# Led_Beleuchtung.net
KiCad netlist of a schematic drawn in EAGLE
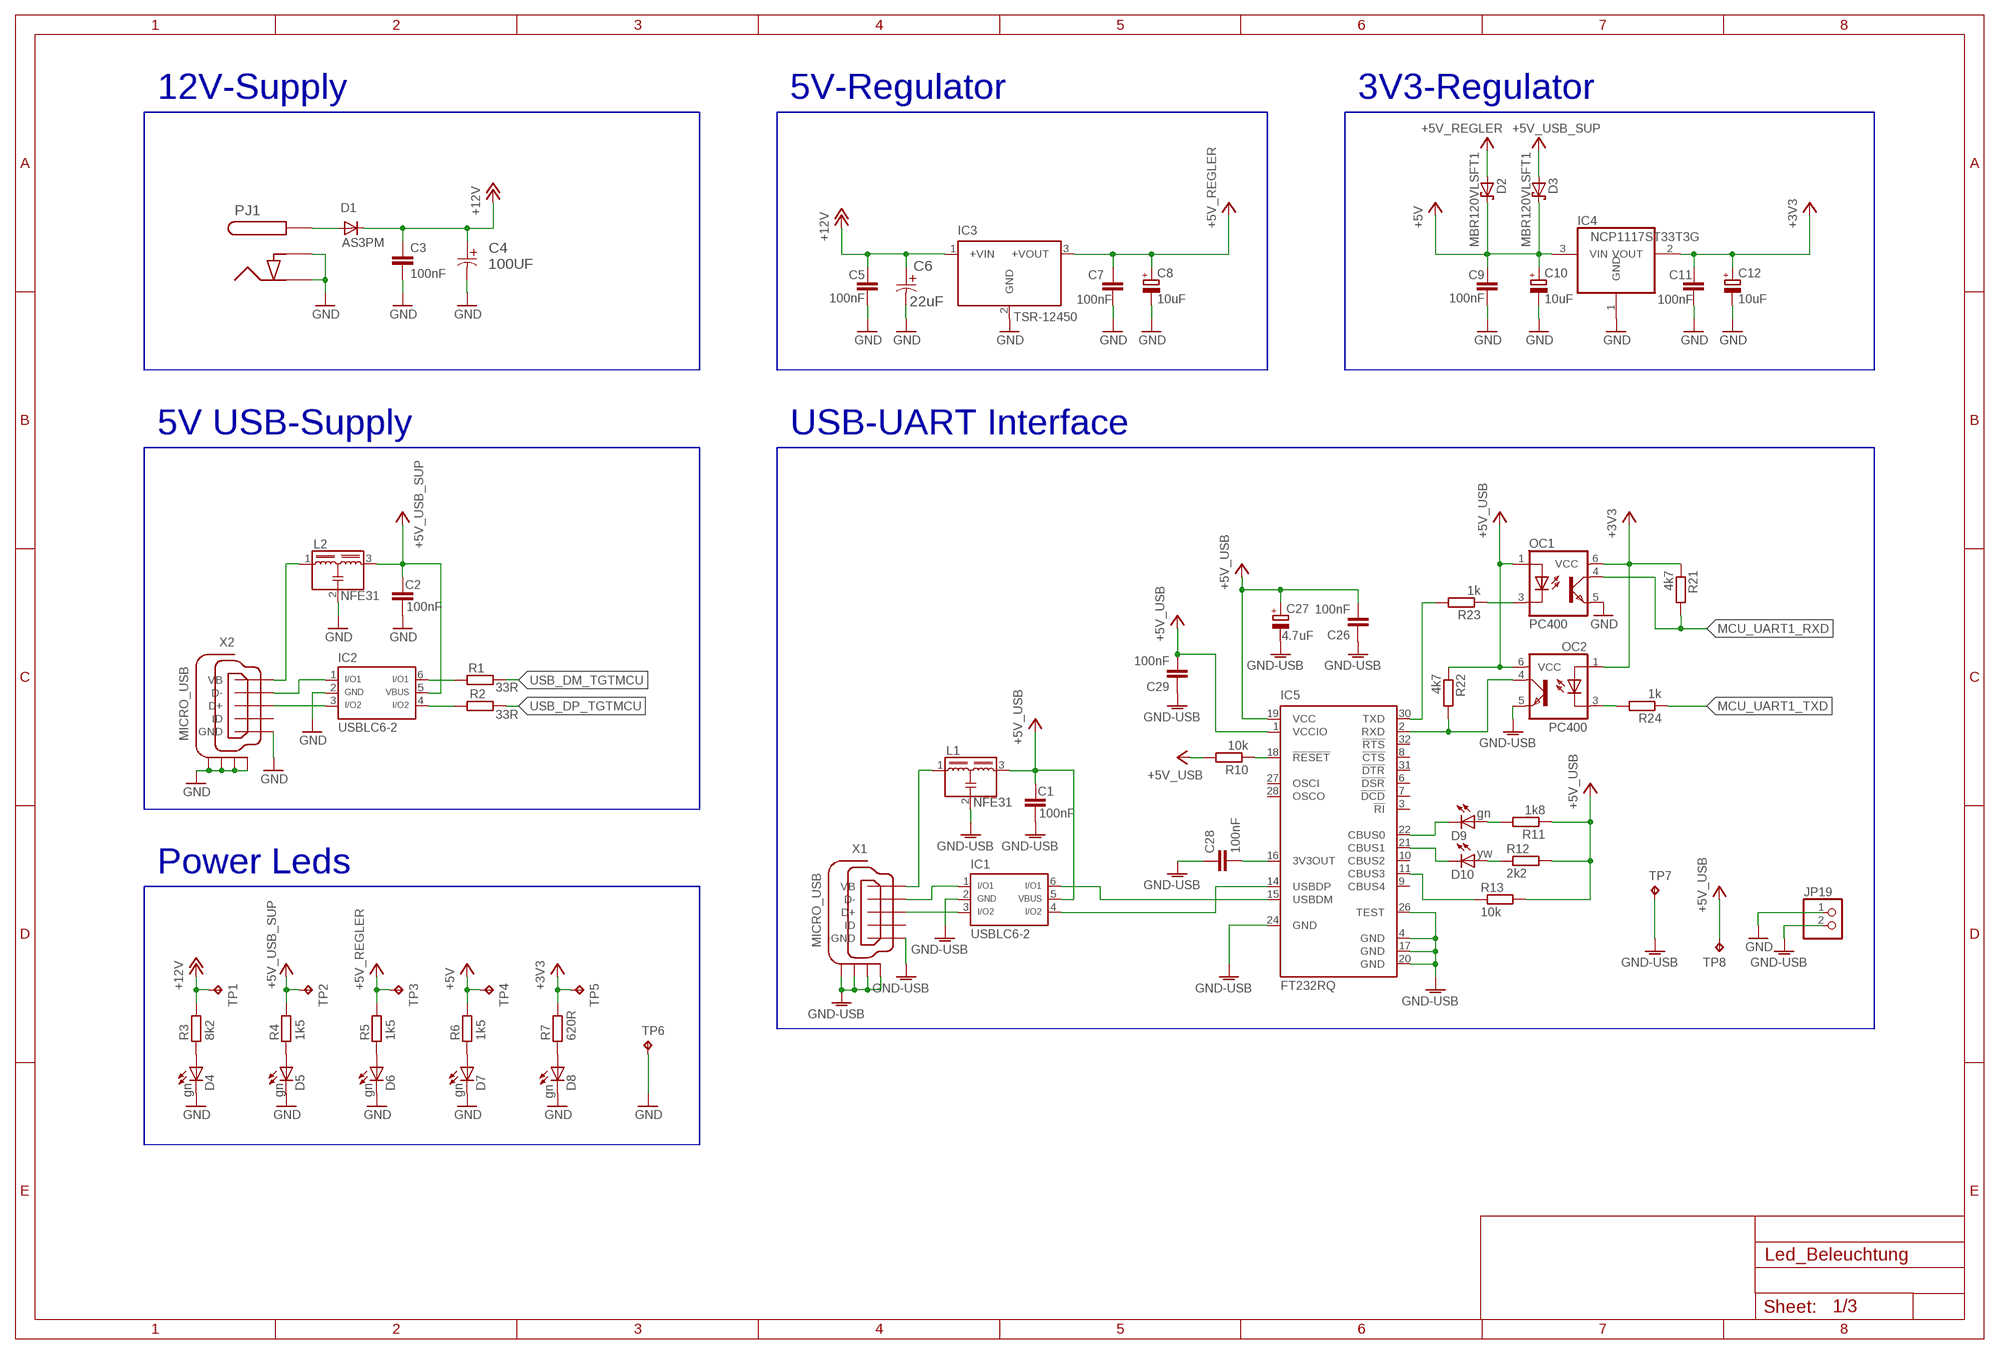
[diagram p0: schematic, sheet 1]
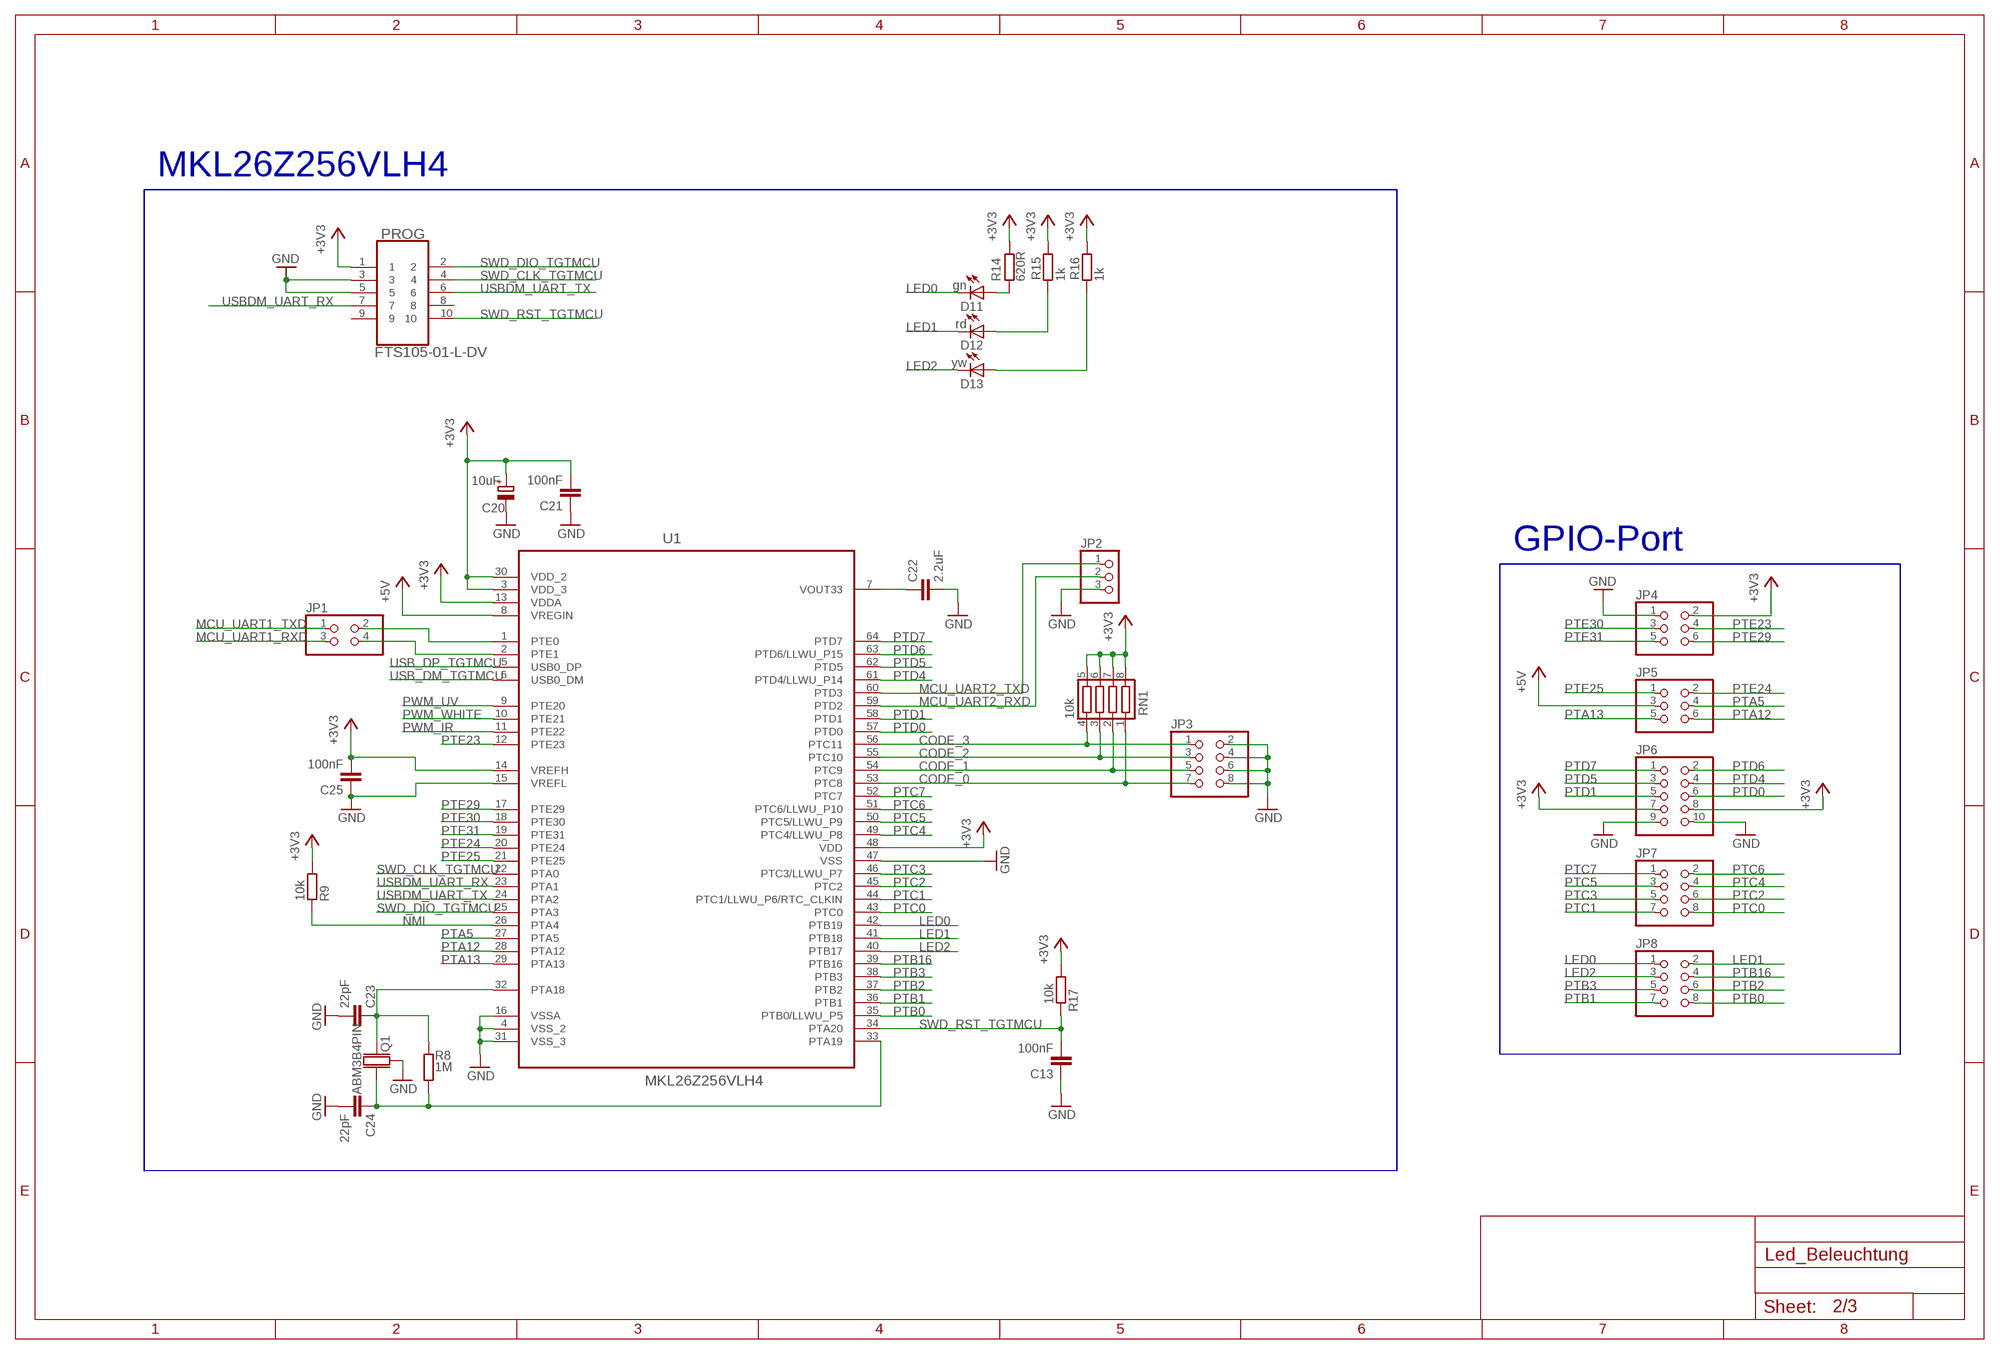
[diagram p1: schematic, sheet 2]
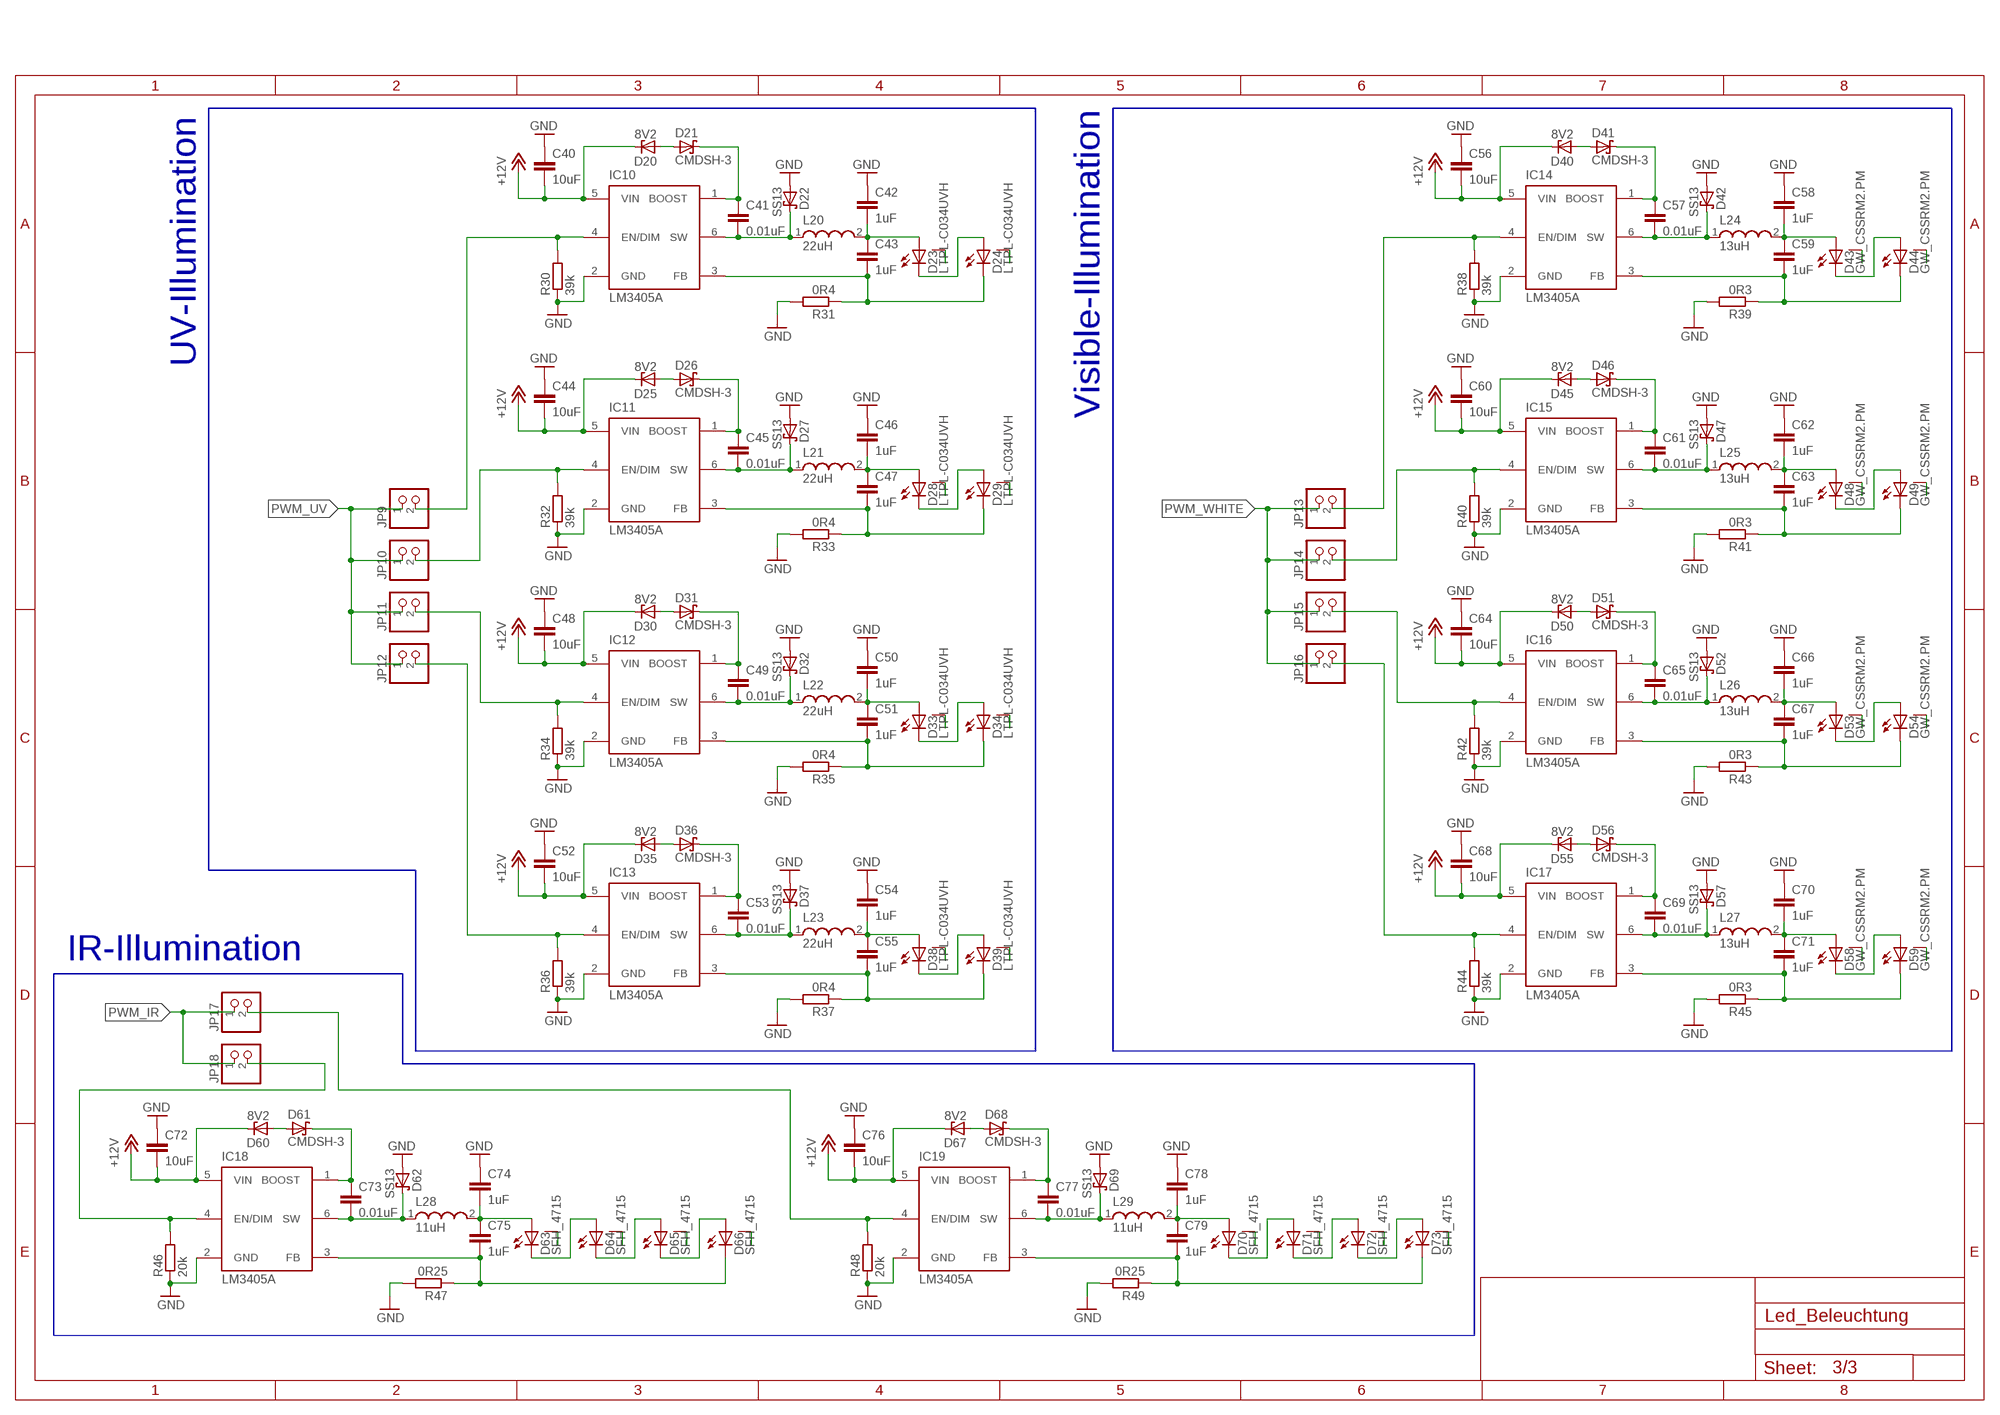
[diagram p2: schematic, sheet 3]

(export (version "E")
  (design (tool "Eeschema 10.0.6"))
  (components
    (comp (ref "C1")
      (value "100nF")
      (footprint "eagle-import:C0603K")
      (libsource (lib "eagle-import") (part "C-EUC0603K"))
    )
    (comp (ref "C2")
      (value "100nF")
      (footprint "eagle-import:C0603K")
      (libsource (lib "eagle-import") (part "C-EUC0603K"))
    )
    (comp (ref "C3")
      (value "100nF")
      (footprint "eagle-import:C0603K")
      (libsource (lib "eagle-import") (part "C-EUC0603K"))
    )
    (comp (ref "C4")
      (value "100UF")
      (footprint "eagle-import:CAPAE660X800N")
      (fields (field (name "MPN") "EEE-FTH101XAP") (field (name "TOLERANCE") "±20 %"))
      (libsource (lib "eagle-import") (part "EEE--CASE-D8FTH101XAP"))
    )
    (comp (ref "C5")
      (value "100nF")
      (footprint "eagle-import:C0603K")
      (libsource (lib "eagle-import") (part "C-EUC0603K"))
    )
    (comp (ref "C6")
      (value "22uF")
      (footprint "eagle-import:CAPAE660X610N")
      (libsource (lib "eagle-import") (part "EEE--CASE-D"))
    )
    (comp (ref "C7")
      (value "100nF")
      (footprint "eagle-import:C0603K")
      (libsource (lib "eagle-import") (part "C-EUC0603K"))
    )
    (comp (ref "C8")
      (value "10uF")
      (footprint "eagle-import:SMC_P")
      (libsource (lib "eagle-import") (part "CPOL_EU0805"))
    )
    (comp (ref "C9")
      (value "100nF")
      (footprint "eagle-import:C0603K")
      (libsource (lib "eagle-import") (part "C-EUC0603K"))
    )
    (comp (ref "C10")
      (value "10uF")
      (footprint "eagle-import:SMC_P")
      (libsource (lib "eagle-import") (part "CPOL_EU0805"))
    )
    (comp (ref "C11")
      (value "100nF")
      (footprint "eagle-import:C0603K")
      (libsource (lib "eagle-import") (part "C-EUC0603K"))
    )
    (comp (ref "C12")
      (value "10uF")
      (footprint "eagle-import:SMC_P")
      (libsource (lib "eagle-import") (part "CPOL_EU0805"))
    )
    (comp (ref "C26")
      (value "100nF")
      (footprint "eagle-import:C0603K")
      (libsource (lib "eagle-import") (part "C-EUC0603K"))
    )
    (comp (ref "C27")
      (value "4.7uF")
      (footprint "eagle-import:SMC_P")
      (libsource (lib "eagle-import") (part "CPOL_EU0805"))
    )
    (comp (ref "C28")
      (value "100nF")
      (footprint "eagle-import:C0603K")
      (libsource (lib "eagle-import") (part "C-EUC0603K"))
    )
    (comp (ref "C29")
      (value "100nF")
      (footprint "eagle-import:C0603")
      (libsource (lib "eagle-import") (part "C-EUC0603"))
    )
    (comp (ref "D1")
      (value "AS3PM")
      (footprint "eagle-import:TO-277A")
      (libsource (lib "eagle-import") (part "AS3PM"))
    )
    (comp (ref "D2")
      (value "MBR120VLSFT1")
      (footprint "eagle-import:SOD-123")
      (libsource (lib "eagle-import") (part "MBR120VLSFT1"))
    )
    (comp (ref "D3")
      (value "MBR120VLSFT1")
      (footprint "eagle-import:SOD-123")
      (libsource (lib "eagle-import") (part "MBR120VLSFT1"))
    )
    (comp (ref "D4")
      (value "gn")
      (footprint "eagle-import:CHIP-LED0603")
      (libsource (lib "eagle-import") (part "LEDCHIP-LED0603"))
    )
    (comp (ref "D5")
      (value "gn")
      (footprint "eagle-import:CHIP-LED0603")
      (libsource (lib "eagle-import") (part "LEDCHIP-LED0603"))
    )
    (comp (ref "D6")
      (value "gn")
      (footprint "eagle-import:CHIP-LED0603")
      (libsource (lib "eagle-import") (part "LEDCHIP-LED0603"))
    )
    (comp (ref "D7")
      (value "gn")
      (footprint "eagle-import:CHIP-LED0603")
      (libsource (lib "eagle-import") (part "LEDCHIP-LED0603"))
    )
    (comp (ref "D8")
      (value "gn")
      (footprint "eagle-import:CHIP-LED0603")
      (libsource (lib "eagle-import") (part "LEDCHIP-LED0603"))
    )
    (comp (ref "D9")
      (value "gn")
      (footprint "eagle-import:CHIP-LED0603")
      (libsource (lib "eagle-import") (part "LEDCHIP-LED0603"))
    )
    (comp (ref "D10")
      (value "yw")
      (footprint "eagle-import:CHIP-LED0603")
      (libsource (lib "eagle-import") (part "LEDCHIP-LED0603"))
    )
    (comp (ref "IC1")
      (value "USBLC6-2")
      (footprint "eagle-import:SOT-23-6L")
      (libsource (lib "eagle-import") (part "USBLC6-2"))
    )
    (comp (ref "IC2")
      (value "USBLC6-2")
      (footprint "eagle-import:SOT-23-6L")
      (libsource (lib "eagle-import") (part "USBLC6-2"))
    )
    (comp (ref "IC3")
      (value "TSR-12450")
      (footprint "eagle-import:TSR-1")
      (libsource (lib "eagle-import") (part "TSR-12450"))
    )
    (comp (ref "IC4")
      (value "NCP1117ST33T3G")
      (footprint "eagle-import:SOT223")
      (fields (field (name "MPN") "REG1117"))
      (libsource (lib "eagle-import") (part "REG1117"))
    )
    (comp (ref "IC5")
      (value "FT232RQ")
      (footprint "eagle-import:QFN32")
      (libsource (lib "eagle-import") (part "FT232RQ"))
    )
    (comp (ref "JP19")
      (value "PINHD-1X2")
      (footprint "eagle-import:1X02")
      (libsource (lib "eagle-import") (part "PINHD-1X2"))
    )
    (comp (ref "L1")
      (value "NFE31")
      (footprint "eagle-import:EMIFILTER")
      (libsource (lib "eagle-import") (part "EMIFIL"))
    )
    (comp (ref "L2")
      (value "NFE31")
      (footprint "eagle-import:EMIFILTER")
      (libsource (lib "eagle-import") (part "EMIFIL"))
    )
    (comp (ref "OC1")
      (value "PC400")
      (footprint "eagle-import:PC400")
      (libsource (lib "eagle-import") (part "PC400"))
    )
    (comp (ref "OC2")
      (value "PC400")
      (footprint "eagle-import:PC400")
      (libsource (lib "eagle-import") (part "PC400"))
    )
    (comp (ref "PJ1")
      (value "PJ-002AH-SMT-TR")
      (footprint "eagle-import:PJ-002AH-SMT-TR")
      (libsource (lib "eagle-import") (part "PJ-002AH-SMT-TR"))
    )
    (comp (ref "R1")
      (value "33R")
      (footprint "eagle-import:R0603")
      (libsource (lib "eagle-import") (part "R-EU_R0603"))
    )
    (comp (ref "R2")
      (value "33R")
      (footprint "eagle-import:R0603")
      (libsource (lib "eagle-import") (part "R-EU_R0603"))
    )
    (comp (ref "R3")
      (value "8k2")
      (footprint "eagle-import:R0603")
      (libsource (lib "eagle-import") (part "R-EU_R0603"))
    )
    (comp (ref "R4")
      (value "1k5")
      (footprint "eagle-import:R0603")
      (libsource (lib "eagle-import") (part "R-EU_R0603"))
    )
    (comp (ref "R5")
      (value "1k5")
      (footprint "eagle-import:R0603")
      (libsource (lib "eagle-import") (part "R-EU_R0603"))
    )
    (comp (ref "R6")
      (value "1k5")
      (footprint "eagle-import:R0603")
      (libsource (lib "eagle-import") (part "R-EU_R0603"))
    )
    (comp (ref "R7")
      (value "620R")
      (footprint "eagle-import:R0603")
      (libsource (lib "eagle-import") (part "R-EU_R0603"))
    )
    (comp (ref "R10")
      (value "10k")
      (footprint "eagle-import:R0603")
      (libsource (lib "eagle-import") (part "R-EU_R0603"))
    )
    (comp (ref "R11")
      (value "1k8")
      (footprint "eagle-import:R0603")
      (libsource (lib "eagle-import") (part "R-EU_R0603"))
    )
    (comp (ref "R12")
      (value "2k2")
      (footprint "eagle-import:R0603")
      (libsource (lib "eagle-import") (part "R-EU_R0603"))
    )
    (comp (ref "R13")
      (value "10k")
      (footprint "eagle-import:R0603")
      (libsource (lib "eagle-import") (part "R-EU_R0603"))
    )
    (comp (ref "R21")
      (value "4k7")
      (footprint "eagle-import:R0603")
      (libsource (lib "eagle-import") (part "R-EU_R0603"))
    )
    (comp (ref "R22")
      (value "4k7")
      (footprint "eagle-import:R0603")
      (libsource (lib "eagle-import") (part "R-EU_R0603"))
    )
    (comp (ref "R23")
      (value "1k")
      (footprint "eagle-import:R0603")
      (libsource (lib "eagle-import") (part "R-EU_R0603"))
    )
    (comp (ref "R24")
      (value "1k")
      (footprint "eagle-import:R0603")
      (libsource (lib "eagle-import") (part "R-EU_R0603"))
    )
    (comp (ref "TP1")
      (value "+12V")
      (footprint "eagle-import:TP08R")
      (libsource (lib "eagle-import") (part "TPTP08R"))
    )
    (comp (ref "TP2")
      (value "+5V_USB")
      (footprint "eagle-import:TP08R")
      (libsource (lib "eagle-import") (part "TPTP08R"))
    )
    (comp (ref "TP3")
      (value "+5V_Reg")
      (footprint "eagle-import:TP08R")
      (libsource (lib "eagle-import") (part "TPTP08R"))
    )
    (comp (ref "TP4")
      (value "+5V")
      (footprint "eagle-import:TP08R")
      (libsource (lib "eagle-import") (part "TPTP08R"))
    )
    (comp (ref "TP5")
      (value "+3V3")
      (footprint "eagle-import:TP08R")
      (libsource (lib "eagle-import") (part "TPTP08R"))
    )
    (comp (ref "TP6")
      (value "GND")
      (footprint "eagle-import:TP08R")
      (libsource (lib "eagle-import") (part "TPTP08R"))
    )
    (comp (ref "TP7")
      (value "GND")
      (footprint "eagle-import:TP08R")
      (libsource (lib "eagle-import") (part "TPTP08R"))
    )
    (comp (ref "TP8")
      (value "+5V")
      (footprint "eagle-import:TP08R")
      (libsource (lib "eagle-import") (part "TPTP08R"))
    )
    (comp (ref "X1")
      (value "MICRO_USB")
      (footprint "eagle-import:MICRO-USB")
      (libsource (lib "eagle-import") (part "MICRO_USB"))
    )
    (comp (ref "X2")
      (value "MICRO_USB")
      (footprint "eagle-import:MICRO-USB")
      (libsource (lib "eagle-import") (part "MICRO_USB"))
    )
    (comp (ref "C13")
      (value "100nF")
      (footprint "eagle-import:C0603")
      (libsource (lib "eagle-import") (part "C-EUC0603"))
    )
    (comp (ref "C20")
      (value "10uF")
      (footprint "eagle-import:SMC_P")
      (libsource (lib "eagle-import") (part "CPOL_EU0805"))
    )
    (comp (ref "C21")
      (value "100nF")
      (footprint "eagle-import:C0603")
      (libsource (lib "eagle-import") (part "C-EUC0603"))
    )
    (comp (ref "C22")
      (value "2.2uF")
      (footprint "eagle-import:C0603")
      (libsource (lib "eagle-import") (part "C-EUC0603"))
    )
    (comp (ref "C23")
      (value "22pF")
      (footprint "eagle-import:C0603")
      (libsource (lib "eagle-import") (part "C-EUC0603"))
    )
    (comp (ref "C24")
      (value "22pF")
      (footprint "eagle-import:C0603")
      (libsource (lib "eagle-import") (part "C-EUC0603"))
    )
    (comp (ref "C25")
      (value "100nF")
      (footprint "eagle-import:C0603K")
      (libsource (lib "eagle-import") (part "C-EUC0603K"))
    )
    (comp (ref "D11")
      (value "gn")
      (footprint "eagle-import:CHIP-LED0603")
      (libsource (lib "eagle-import") (part "LEDCHIP-LED0603"))
    )
    (comp (ref "D12")
      (value "rd")
      (footprint "eagle-import:CHIP-LED0603")
      (libsource (lib "eagle-import") (part "LEDCHIP-LED0603"))
    )
    (comp (ref "D13")
      (value "yw")
      (footprint "eagle-import:CHIP-LED0603")
      (libsource (lib "eagle-import") (part "LEDCHIP-LED0603"))
    )
    (comp (ref "JP1")
      (value "PINHD-2X2")
      (footprint "eagle-import:2X02")
      (libsource (lib "eagle-import") (part "PINHD-2X2"))
    )
    (comp (ref "JP2")
      (value "BCH-381H-3GN")
      (footprint "eagle-import:BCH-381H-3GN")
      (libsource (lib "eagle-import") (part "BCH-381H-3GN"))
    )
    (comp (ref "JP3")
      (value "PINHD-2X4")
      (footprint "eagle-import:2X04")
      (libsource (lib "eagle-import") (part "PINHD-2X4"))
    )
    (comp (ref "JP4")
      (value "PINHD-2X3")
      (footprint "eagle-import:2X03")
      (libsource (lib "eagle-import") (part "PINHD-2X3"))
    )
    (comp (ref "JP5")
      (value "PINHD-2X3")
      (footprint "eagle-import:2X03")
      (libsource (lib "eagle-import") (part "PINHD-2X3"))
    )
    (comp (ref "JP6")
      (value "PINHD-2X5")
      (footprint "eagle-import:2X05")
      (libsource (lib "eagle-import") (part "PINHD-2X5"))
    )
    (comp (ref "JP7")
      (value "PINHD-2X4")
      (footprint "eagle-import:2X04")
      (libsource (lib "eagle-import") (part "PINHD-2X4"))
    )
    (comp (ref "JP8")
      (value "PINHD-2X4")
      (footprint "eagle-import:2X04")
      (libsource (lib "eagle-import") (part "PINHD-2X4"))
    )
    (comp (ref "PROG")
      (value "FTS105-01-L-DV")
      (footprint "eagle-import:SAMTEC_FTS105-01-L-DV")
      (libsource (lib "eagle-import") (part "FTS105-01-L-DV"))
    )
    (comp (ref "Q1")
      (value "ABM3B4PIN")
      (footprint "eagle-import:ABM3B")
      (libsource (lib "eagle-import") (part "ABM3B4PIN"))
    )
    (comp (ref "R8")
      (value "1M")
      (footprint "eagle-import:R0603")
      (libsource (lib "eagle-import") (part "R-EU_R0603"))
    )
    (comp (ref "R9")
      (value "10k")
      (footprint "eagle-import:R0603")
      (libsource (lib "eagle-import") (part "R-EU_R0603"))
    )
    (comp (ref "R14")
      (value "620R")
      (footprint "eagle-import:R0603")
      (libsource (lib "eagle-import") (part "R-EU_R0603"))
    )
    (comp (ref "R15")
      (value "1k")
      (footprint "eagle-import:R0603")
      (libsource (lib "eagle-import") (part "R-EU_R0603"))
    )
    (comp (ref "R16")
      (value "1k")
      (footprint "eagle-import:R0603")
      (libsource (lib "eagle-import") (part "R-EU_R0603"))
    )
    (comp (ref "R17")
      (value "10k")
      (footprint "eagle-import:R0603")
      (libsource (lib "eagle-import") (part "R-EU_R0603"))
    )
    (comp (ref "RN1")
      (value "10k")
      (footprint "eagle-import:CTS742C083")
      (libsource (lib "eagle-import") (part "CTS742C083"))
    )
    (comp (ref "U1")
      (value "MKL26Z256VLH4")
      (footprint "eagle-import:QFP50P1200X1200X160-64N")
      (libsource (lib "eagle-import") (part "MKL26Z256VLH4"))
    )
    (comp (ref "C40")
      (value "10uF")
      (footprint "eagle-import:C1206K")
      (libsource (lib "eagle-import") (part "C-EUC1206K"))
    )
    (comp (ref "C41")
      (value "0.01uF")
      (footprint "eagle-import:C0805K")
      (libsource (lib "eagle-import") (part "C-EUC0805K"))
    )
    (comp (ref "C42")
      (value "1uF")
      (footprint "eagle-import:C1206K")
      (libsource (lib "eagle-import") (part "C-EUC1206K"))
    )
    (comp (ref "C43")
      (value "1uF")
      (footprint "eagle-import:C1206K")
      (libsource (lib "eagle-import") (part "C-EUC1206K"))
    )
    (comp (ref "C44")
      (value "10uF")
      (footprint "eagle-import:C1206K")
      (libsource (lib "eagle-import") (part "C-EUC1206K"))
    )
    (comp (ref "C45")
      (value "0.01uF")
      (footprint "eagle-import:C0805K")
      (libsource (lib "eagle-import") (part "C-EUC0805K"))
    )
    (comp (ref "C46")
      (value "1uF")
      (footprint "eagle-import:C1206K")
      (libsource (lib "eagle-import") (part "C-EUC1206K"))
    )
    (comp (ref "C47")
      (value "1uF")
      (footprint "eagle-import:C1206K")
      (libsource (lib "eagle-import") (part "C-EUC1206K"))
    )
    (comp (ref "C48")
      (value "10uF")
      (footprint "eagle-import:C1206K")
      (libsource (lib "eagle-import") (part "C-EUC1206K"))
    )
    (comp (ref "C49")
      (value "0.01uF")
      (footprint "eagle-import:C0805K")
      (libsource (lib "eagle-import") (part "C-EUC0805K"))
    )
    (comp (ref "C50")
      (value "1uF")
      (footprint "eagle-import:C1206K")
      (libsource (lib "eagle-import") (part "C-EUC1206K"))
    )
    (comp (ref "C51")
      (value "1uF")
      (footprint "eagle-import:C1206K")
      (libsource (lib "eagle-import") (part "C-EUC1206K"))
    )
    (comp (ref "C52")
      (value "10uF")
      (footprint "eagle-import:C1206K")
      (libsource (lib "eagle-import") (part "C-EUC1206K"))
    )
    (comp (ref "C53")
      (value "0.01uF")
      (footprint "eagle-import:C0805K")
      (libsource (lib "eagle-import") (part "C-EUC0805K"))
    )
    (comp (ref "C54")
      (value "1uF")
      (footprint "eagle-import:C1206K")
      (libsource (lib "eagle-import") (part "C-EUC1206K"))
    )
    (comp (ref "C55")
      (value "1uF")
      (footprint "eagle-import:C1206K")
      (libsource (lib "eagle-import") (part "C-EUC1206K"))
    )
    (comp (ref "C56")
      (value "10uF")
      (footprint "eagle-import:C1206K")
      (libsource (lib "eagle-import") (part "C-EUC1206K"))
    )
    (comp (ref "C57")
      (value "0.01uF")
      (footprint "eagle-import:C0805K")
      (libsource (lib "eagle-import") (part "C-EUC0805K"))
    )
    (comp (ref "C58")
      (value "1uF")
      (footprint "eagle-import:C1206K")
      (libsource (lib "eagle-import") (part "C-EUC1206K"))
    )
    (comp (ref "C59")
      (value "1uF")
      (footprint "eagle-import:C1206K")
      (libsource (lib "eagle-import") (part "C-EUC1206K"))
    )
    (comp (ref "C60")
      (value "10uF")
      (footprint "eagle-import:C1206K")
      (libsource (lib "eagle-import") (part "C-EUC1206K"))
    )
    (comp (ref "C61")
      (value "0.01uF")
      (footprint "eagle-import:C0805K")
      (libsource (lib "eagle-import") (part "C-EUC0805K"))
    )
    (comp (ref "C62")
      (value "1uF")
      (footprint "eagle-import:C1206K")
      (libsource (lib "eagle-import") (part "C-EUC1206K"))
    )
    (comp (ref "C63")
      (value "1uF")
      (footprint "eagle-import:C1206K")
      (libsource (lib "eagle-import") (part "C-EUC1206K"))
    )
    (comp (ref "C64")
      (value "10uF")
      (footprint "eagle-import:C1206K")
      (libsource (lib "eagle-import") (part "C-EUC1206K"))
    )
    (comp (ref "C65")
      (value "0.01uF")
      (footprint "eagle-import:C0805K")
      (libsource (lib "eagle-import") (part "C-EUC0805K"))
    )
    (comp (ref "C66")
      (value "1uF")
      (footprint "eagle-import:C1206K")
      (libsource (lib "eagle-import") (part "C-EUC1206K"))
    )
    (comp (ref "C67")
      (value "1uF")
      (footprint "eagle-import:C1206K")
      (libsource (lib "eagle-import") (part "C-EUC1206K"))
    )
    (comp (ref "C68")
      (value "10uF")
      (footprint "eagle-import:C1206K")
      (libsource (lib "eagle-import") (part "C-EUC1206K"))
    )
    (comp (ref "C69")
      (value "0.01uF")
      (footprint "eagle-import:C0805K")
      (libsource (lib "eagle-import") (part "C-EUC0805K"))
    )
    (comp (ref "C70")
      (value "1uF")
      (footprint "eagle-import:C1206K")
      (libsource (lib "eagle-import") (part "C-EUC1206K"))
    )
    (comp (ref "C71")
      (value "1uF")
      (footprint "eagle-import:C1206K")
      (libsource (lib "eagle-import") (part "C-EUC1206K"))
    )
    (comp (ref "C72")
      (value "10uF")
      (footprint "eagle-import:C1206K")
      (libsource (lib "eagle-import") (part "C-EUC1206K"))
    )
    (comp (ref "C73")
      (value "0.01uF")
      (footprint "eagle-import:C0805K")
      (libsource (lib "eagle-import") (part "C-EUC0805K"))
    )
    (comp (ref "C74")
      (value "1uF")
      (footprint "eagle-import:C1206K")
      (libsource (lib "eagle-import") (part "C-EUC1206K"))
    )
    (comp (ref "C75")
      (value "1uF")
      (footprint "eagle-import:C1206K")
      (libsource (lib "eagle-import") (part "C-EUC1206K"))
    )
    (comp (ref "C76")
      (value "10uF")
      (footprint "eagle-import:C1206K")
      (libsource (lib "eagle-import") (part "C-EUC1206K"))
    )
    (comp (ref "C77")
      (value "0.01uF")
      (footprint "eagle-import:C0805K")
      (libsource (lib "eagle-import") (part "C-EUC0805K"))
    )
    (comp (ref "C78")
      (value "1uF")
      (footprint "eagle-import:C1206K")
      (libsource (lib "eagle-import") (part "C-EUC1206K"))
    )
    (comp (ref "C79")
      (value "1uF")
      (footprint "eagle-import:C1206K")
      (libsource (lib "eagle-import") (part "C-EUC1206K"))
    )
    (comp (ref "D20")
      (value "8V2")
      (footprint "eagle-import:SOT23")
      (libsource (lib "eagle-import") (part "ZENER-DIODESOT23"))
    )
    (comp (ref "D21")
      (value "CMDSH-3")
      (footprint "eagle-import:SOD323")
      (libsource (lib "eagle-import") (part "CMDSH-3"))
    )
    (comp (ref "D22")
      (value "SS13")
      (footprint "eagle-import:DO-214AC")
      (libsource (lib "eagle-import") (part "SS13"))
    )
    (comp (ref "D23")
      (value "LTPL-C034UVH")
      (footprint "eagle-import:LTPL-C034UVH")
      (libsource (lib "eagle-import") (part "LTPL-C034UVH"))
    )
    (comp (ref "D24")
      (value "LTPL-C034UVH")
      (footprint "eagle-import:LTPL-C034UVH")
      (libsource (lib "eagle-import") (part "LTPL-C034UVH"))
    )
    (comp (ref "D25")
      (value "8V2")
      (footprint "eagle-import:SOT23")
      (libsource (lib "eagle-import") (part "ZENER-DIODESOT23"))
    )
    (comp (ref "D26")
      (value "CMDSH-3")
      (footprint "eagle-import:SOD323")
      (libsource (lib "eagle-import") (part "CMDSH-3"))
    )
    (comp (ref "D27")
      (value "SS13")
      (footprint "eagle-import:DO-214AC")
      (libsource (lib "eagle-import") (part "SS13"))
    )
    (comp (ref "D28")
      (value "LTPL-C034UVH")
      (footprint "eagle-import:LTPL-C034UVH")
      (libsource (lib "eagle-import") (part "LTPL-C034UVH"))
    )
    (comp (ref "D29")
      (value "LTPL-C034UVH")
      (footprint "eagle-import:LTPL-C034UVH")
      (libsource (lib "eagle-import") (part "LTPL-C034UVH"))
    )
    (comp (ref "D30")
      (value "8V2")
      (footprint "eagle-import:SOT23")
      (libsource (lib "eagle-import") (part "ZENER-DIODESOT23"))
    )
    (comp (ref "D31")
      (value "CMDSH-3")
      (footprint "eagle-import:SOD323")
      (libsource (lib "eagle-import") (part "CMDSH-3"))
    )
    (comp (ref "D32")
      (value "SS13")
      (footprint "eagle-import:DO-214AC")
      (libsource (lib "eagle-import") (part "SS13"))
    )
    (comp (ref "D33")
      (value "LTPL-C034UVH")
      (footprint "eagle-import:LTPL-C034UVH")
      (libsource (lib "eagle-import") (part "LTPL-C034UVH"))
    )
    (comp (ref "D34")
      (value "LTPL-C034UVH")
      (footprint "eagle-import:LTPL-C034UVH")
      (libsource (lib "eagle-import") (part "LTPL-C034UVH"))
    )
    (comp (ref "D35")
      (value "8V2")
      (footprint "eagle-import:SOT23")
      (libsource (lib "eagle-import") (part "ZENER-DIODESOT23"))
    )
    (comp (ref "D36")
      (value "CMDSH-3")
      (footprint "eagle-import:SOD323")
      (libsource (lib "eagle-import") (part "CMDSH-3"))
    )
    (comp (ref "D37")
      (value "SS13")
      (footprint "eagle-import:DO-214AC")
      (libsource (lib "eagle-import") (part "SS13"))
    )
    (comp (ref "D38")
      (value "LTPL-C034UVH")
      (footprint "eagle-import:LTPL-C034UVH")
      (libsource (lib "eagle-import") (part "LTPL-C034UVH"))
    )
    (comp (ref "D39")
      (value "LTPL-C034UVH")
      (footprint "eagle-import:LTPL-C034UVH")
      (libsource (lib "eagle-import") (part "LTPL-C034UVH"))
    )
    (comp (ref "D40")
      (value "8V2")
      (footprint "eagle-import:SOT23")
      (libsource (lib "eagle-import") (part "ZENER-DIODESOT23"))
    )
    (comp (ref "D41")
      (value "CMDSH-3")
      (footprint "eagle-import:SOD323")
      (libsource (lib "eagle-import") (part "CMDSH-3"))
    )
    (comp (ref "D42")
      (value "SS13")
      (footprint "eagle-import:DO-214AC")
      (libsource (lib "eagle-import") (part "SS13"))
    )
    (comp (ref "D43")
      (value "GW_CSSRM2.PM")
      (footprint "eagle-import:GW_CSSRM2.PM")
      (libsource (lib "eagle-import") (part "GW_CSSRM2.PM"))
    )
    (comp (ref "D44")
      (value "GW_CSSRM2.PM")
      (footprint "eagle-import:GW_CSSRM2.PM")
      (libsource (lib "eagle-import") (part "GW_CSSRM2.PM"))
    )
    (comp (ref "D45")
      (value "8V2")
      (footprint "eagle-import:SOT23")
      (libsource (lib "eagle-import") (part "ZENER-DIODESOT23"))
    )
    (comp (ref "D46")
      (value "CMDSH-3")
      (footprint "eagle-import:SOD323")
      (libsource (lib "eagle-import") (part "CMDSH-3"))
    )
    (comp (ref "D47")
      (value "SS13")
      (footprint "eagle-import:DO-214AC")
      (libsource (lib "eagle-import") (part "SS13"))
    )
    (comp (ref "D48")
      (value "GW_CSSRM2.PM")
      (footprint "eagle-import:GW_CSSRM2.PM")
      (libsource (lib "eagle-import") (part "GW_CSSRM2.PM"))
    )
    (comp (ref "D49")
      (value "GW_CSSRM2.PM")
      (footprint "eagle-import:GW_CSSRM2.PM")
      (libsource (lib "eagle-import") (part "GW_CSSRM2.PM"))
    )
    (comp (ref "D50")
      (value "8V2")
      (footprint "eagle-import:SOT23")
      (libsource (lib "eagle-import") (part "ZENER-DIODESOT23"))
    )
    (comp (ref "D51")
      (value "CMDSH-3")
      (footprint "eagle-import:SOD323")
      (libsource (lib "eagle-import") (part "CMDSH-3"))
    )
    (comp (ref "D52")
      (value "SS13")
      (footprint "eagle-import:DO-214AC")
      (libsource (lib "eagle-import") (part "SS13"))
    )
    (comp (ref "D53")
      (value "GW_CSSRM2.PM")
      (footprint "eagle-import:GW_CSSRM2.PM")
      (libsource (lib "eagle-import") (part "GW_CSSRM2.PM"))
    )
    (comp (ref "D54")
      (value "GW_CSSRM2.PM")
      (footprint "eagle-import:GW_CSSRM2.PM")
      (libsource (lib "eagle-import") (part "GW_CSSRM2.PM"))
    )
    (comp (ref "D55")
      (value "8V2")
      (footprint "eagle-import:SOT23")
      (libsource (lib "eagle-import") (part "ZENER-DIODESOT23"))
    )
    (comp (ref "D56")
      (value "CMDSH-3")
      (footprint "eagle-import:SOD323")
      (libsource (lib "eagle-import") (part "CMDSH-3"))
    )
    (comp (ref "D57")
      (value "SS13")
      (footprint "eagle-import:DO-214AC")
      (libsource (lib "eagle-import") (part "SS13"))
    )
    (comp (ref "D58")
      (value "GW_CSSRM2.PM")
      (footprint "eagle-import:GW_CSSRM2.PM")
      (libsource (lib "eagle-import") (part "GW_CSSRM2.PM"))
    )
    (comp (ref "D59")
      (value "GW_CSSRM2.PM")
      (footprint "eagle-import:GW_CSSRM2.PM")
      (libsource (lib "eagle-import") (part "GW_CSSRM2.PM"))
    )
    (comp (ref "D60")
      (value "8V2")
      (footprint "eagle-import:SOT23")
      (libsource (lib "eagle-import") (part "ZENER-DIODESOT23"))
    )
    (comp (ref "D61")
      (value "CMDSH-3")
      (footprint "eagle-import:SOD323")
      (libsource (lib "eagle-import") (part "CMDSH-3"))
    )
    (comp (ref "D62")
      (value "SS13")
      (footprint "eagle-import:DO-214AC")
      (libsource (lib "eagle-import") (part "SS13"))
    )
    (comp (ref "D63")
      (value "SFH_4715")
      (footprint "eagle-import:SFH_4715")
      (libsource (lib "eagle-import") (part "SFH_4715"))
    )
    (comp (ref "D64")
      (value "SFH_4715")
      (footprint "eagle-import:SFH_4715")
      (libsource (lib "eagle-import") (part "SFH_4715"))
    )
    (comp (ref "D65")
      (value "SFH_4715")
      (footprint "eagle-import:SFH_4715")
      (libsource (lib "eagle-import") (part "SFH_4715"))
    )
    (comp (ref "D66")
      (value "SFH_4715")
      (footprint "eagle-import:SFH_4715")
      (libsource (lib "eagle-import") (part "SFH_4715"))
    )
    (comp (ref "D67")
      (value "8V2")
      (footprint "eagle-import:SOT23")
      (libsource (lib "eagle-import") (part "ZENER-DIODESOT23"))
    )
    (comp (ref "D68")
      (value "CMDSH-3")
      (footprint "eagle-import:SOD323")
      (libsource (lib "eagle-import") (part "CMDSH-3"))
    )
    (comp (ref "D69")
      (value "SS13")
      (footprint "eagle-import:DO-214AC")
      (libsource (lib "eagle-import") (part "SS13"))
    )
    (comp (ref "D70")
      (value "SFH_4715")
      (footprint "eagle-import:SFH_4715")
      (libsource (lib "eagle-import") (part "SFH_4715"))
    )
    (comp (ref "D71")
      (value "SFH_4715")
      (footprint "eagle-import:SFH_4715")
      (libsource (lib "eagle-import") (part "SFH_4715"))
    )
    (comp (ref "D72")
      (value "SFH_4715")
      (footprint "eagle-import:SFH_4715")
      (libsource (lib "eagle-import") (part "SFH_4715"))
    )
    (comp (ref "D73")
      (value "SFH_4715")
      (footprint "eagle-import:SFH_4715")
      (libsource (lib "eagle-import") (part "SFH_4715"))
    )
    (comp (ref "IC10")
      (value "LM3405A")
      (footprint "eagle-import:DDC6_SOT")
      (libsource (lib "eagle-import") (part "LM3405A"))
    )
    (comp (ref "IC11")
      (value "LM3405A")
      (footprint "eagle-import:DDC6_SOT")
      (libsource (lib "eagle-import") (part "LM3405A"))
    )
    (comp (ref "IC12")
      (value "LM3405A")
      (footprint "eagle-import:DDC6_SOT")
      (libsource (lib "eagle-import") (part "LM3405A"))
    )
    (comp (ref "IC13")
      (value "LM3405A")
      (footprint "eagle-import:DDC6_SOT")
      (libsource (lib "eagle-import") (part "LM3405A"))
    )
    (comp (ref "IC14")
      (value "LM3405A")
      (footprint "eagle-import:DDC6_SOT")
      (libsource (lib "eagle-import") (part "LM3405A"))
    )
    (comp (ref "IC15")
      (value "LM3405A")
      (footprint "eagle-import:DDC6_SOT")
      (libsource (lib "eagle-import") (part "LM3405A"))
    )
    (comp (ref "IC16")
      (value "LM3405A")
      (footprint "eagle-import:DDC6_SOT")
      (libsource (lib "eagle-import") (part "LM3405A"))
    )
    (comp (ref "IC17")
      (value "LM3405A")
      (footprint "eagle-import:DDC6_SOT")
      (libsource (lib "eagle-import") (part "LM3405A"))
    )
    (comp (ref "IC18")
      (value "LM3405A")
      (footprint "eagle-import:DDC6_SOT")
      (libsource (lib "eagle-import") (part "LM3405A"))
    )
    (comp (ref "IC19")
      (value "LM3405A")
      (footprint "eagle-import:DDC6_SOT")
      (libsource (lib "eagle-import") (part "LM3405A"))
    )
    (comp (ref "JP9")
      (value "PINHD-1X2")
      (footprint "eagle-import:1X02")
      (libsource (lib "eagle-import") (part "PINHD-1X2"))
    )
    (comp (ref "JP10")
      (value "PINHD-1X2")
      (footprint "eagle-import:1X02")
      (libsource (lib "eagle-import") (part "PINHD-1X2"))
    )
    (comp (ref "JP11")
      (value "PINHD-1X2")
      (footprint "eagle-import:1X02")
      (libsource (lib "eagle-import") (part "PINHD-1X2"))
    )
    (comp (ref "JP12")
      (value "PINHD-1X2")
      (footprint "eagle-import:1X02")
      (libsource (lib "eagle-import") (part "PINHD-1X2"))
    )
    (comp (ref "JP13")
      (value "PINHD-1X2")
      (footprint "eagle-import:1X02")
      (libsource (lib "eagle-import") (part "PINHD-1X2"))
    )
    (comp (ref "JP14")
      (value "PINHD-1X2")
      (footprint "eagle-import:1X02")
      (libsource (lib "eagle-import") (part "PINHD-1X2"))
    )
    (comp (ref "JP15")
      (value "PINHD-1X2")
      (footprint "eagle-import:1X02")
      (libsource (lib "eagle-import") (part "PINHD-1X2"))
    )
    (comp (ref "JP16")
      (value "PINHD-1X2")
      (footprint "eagle-import:1X02")
      (libsource (lib "eagle-import") (part "PINHD-1X2"))
    )
    (comp (ref "JP17")
      (value "PINHD-1X2")
      (footprint "eagle-import:1X02")
      (libsource (lib "eagle-import") (part "PINHD-1X2"))
    )
    (comp (ref "JP18")
      (value "PINHD-1X2")
      (footprint "eagle-import:1X02")
      (libsource (lib "eagle-import") (part "PINHD-1X2"))
    )
    (comp (ref "L20")
      (value "22uH")
      (footprint "eagle-import:WE-PDF")
      (libsource (lib "eagle-import") (part "WE-PDF_1064"))
    )
    (comp (ref "L21")
      (value "22uH")
      (footprint "eagle-import:WE-PDF")
      (libsource (lib "eagle-import") (part "WE-PDF_1064"))
    )
    (comp (ref "L22")
      (value "22uH")
      (footprint "eagle-import:WE-PDF")
      (libsource (lib "eagle-import") (part "WE-PDF_1064"))
    )
    (comp (ref "L23")
      (value "22uH")
      (footprint "eagle-import:WE-PDF")
      (libsource (lib "eagle-import") (part "WE-PDF_1064"))
    )
    (comp (ref "L24")
      (value "13uH")
      (footprint "eagle-import:WE-PDF")
      (libsource (lib "eagle-import") (part "WE-PDF_1064"))
    )
    (comp (ref "L25")
      (value "13uH")
      (footprint "eagle-import:WE-PDF")
      (libsource (lib "eagle-import") (part "WE-PDF_1064"))
    )
    (comp (ref "L26")
      (value "13uH")
      (footprint "eagle-import:WE-PDF")
      (libsource (lib "eagle-import") (part "WE-PDF_1064"))
    )
    (comp (ref "L27")
      (value "13uH")
      (footprint "eagle-import:WE-PDF")
      (libsource (lib "eagle-import") (part "WE-PDF_1064"))
    )
    (comp (ref "L28")
      (value "11uH")
      (footprint "eagle-import:WE-PDF")
      (libsource (lib "eagle-import") (part "WE-PDF_1064"))
    )
    (comp (ref "L29")
      (value "11uH")
      (footprint "eagle-import:WE-PDF")
      (libsource (lib "eagle-import") (part "WE-PDF_1064"))
    )
    (comp (ref "R30")
      (value "39k")
      (footprint "eagle-import:R0603")
      (libsource (lib "eagle-import") (part "R-EU_R0603"))
    )
    (comp (ref "R31")
      (value "0R4")
      (footprint "eagle-import:R2010")
      (libsource (lib "eagle-import") (part "R-EU_R2010"))
    )
    (comp (ref "R32")
      (value "39k")
      (footprint "eagle-import:R0603")
      (libsource (lib "eagle-import") (part "R-EU_R0603"))
    )
    (comp (ref "R33")
      (value "0R4")
      (footprint "eagle-import:R2010")
      (libsource (lib "eagle-import") (part "R-EU_R2010"))
    )
    (comp (ref "R34")
      (value "39k")
      (footprint "eagle-import:R0603")
      (libsource (lib "eagle-import") (part "R-EU_R0603"))
    )
    (comp (ref "R35")
      (value "0R4")
      (footprint "eagle-import:R2010")
      (libsource (lib "eagle-import") (part "R-EU_R2010"))
    )
    (comp (ref "R36")
      (value "39k")
      (footprint "eagle-import:R0603")
      (libsource (lib "eagle-import") (part "R-EU_R0603"))
    )
    (comp (ref "R37")
      (value "0R4")
      (footprint "eagle-import:R2010")
      (libsource (lib "eagle-import") (part "R-EU_R2010"))
    )
    (comp (ref "R38")
      (value "39k")
      (footprint "eagle-import:R0603")
      (libsource (lib "eagle-import") (part "R-EU_R0603"))
    )
    (comp (ref "R39")
      (value "0R3")
      (footprint "eagle-import:R2010")
      (libsource (lib "eagle-import") (part "R-EU_R2010"))
    )
    (comp (ref "R40")
      (value "39k")
      (footprint "eagle-import:R0603")
      (libsource (lib "eagle-import") (part "R-EU_R0603"))
    )
    (comp (ref "R41")
      (value "0R3")
      (footprint "eagle-import:R2010")
      (libsource (lib "eagle-import") (part "R-EU_R2010"))
    )
    (comp (ref "R42")
      (value "39k")
      (footprint "eagle-import:R0603")
      (libsource (lib "eagle-import") (part "R-EU_R0603"))
    )
    (comp (ref "R43")
      (value "0R3")
      (footprint "eagle-import:R2010")
      (libsource (lib "eagle-import") (part "R-EU_R2010"))
    )
    (comp (ref "R44")
      (value "39k")
      (footprint "eagle-import:R0603")
      (libsource (lib "eagle-import") (part "R-EU_R0603"))
    )
    (comp (ref "R45")
      (value "0R3")
      (footprint "eagle-import:R2010")
      (libsource (lib "eagle-import") (part "R-EU_R2010"))
    )
    (comp (ref "R46")
      (value "20k")
      (footprint "eagle-import:R0603")
      (libsource (lib "eagle-import") (part "R-EU_R0603"))
    )
    (comp (ref "R47")
      (value "0R25")
      (footprint "eagle-import:R2010")
      (libsource (lib "eagle-import") (part "R-EU_R2010"))
    )
    (comp (ref "R48")
      (value "20k")
      (footprint "eagle-import:R0603")
      (libsource (lib "eagle-import") (part "R-EU_R0603"))
    )
    (comp (ref "R49")
      (value "0R25")
      (footprint "eagle-import:R2010")
      (libsource (lib "eagle-import") (part "R-EU_R2010"))
    )
  )
  (nets
    (net (code "1") (name "+3V3") (class "Default")
      (node (ref "C11") (pin "2") (pinfunction "2_2") (pintype "passive"))
      (node (ref "C12") (pin "+") (pinfunction "+_+") (pintype "passive"))
      (node (ref "C20") (pin "+") (pinfunction "+_+") (pintype "passive"))
      (node (ref "C21") (pin "2") (pinfunction "2_2") (pintype "passive"))
      (node (ref "C25") (pin "2") (pinfunction "2_2") (pintype "passive"))
      (node (ref "IC4") (pin "2") (pinfunction "VOUT_2") (pintype "output"))
      (node (ref "JP4") (pin "2") (pinfunction "2_2") (pintype "passive"))
      (node (ref "JP6") (pin "7") (pinfunction "7_7") (pintype "passive"))
      (node (ref "JP6") (pin "8") (pinfunction "8_8") (pintype "passive"))
      (node (ref "OC1") (pin "6") (pinfunction "VCC_6") (pintype "bidirectional"))
      (node (ref "OC2") (pin "1") (pinfunction "A_1") (pintype "passive"))
      (node (ref "PROG") (pin "1") (pinfunction "1_1") (pintype "passive"))
      (node (ref "R14") (pin "2") (pinfunction "2_2") (pintype "passive"))
      (node (ref "R15") (pin "2") (pinfunction "2_2") (pintype "passive"))
      (node (ref "R16") (pin "2") (pinfunction "2_2") (pintype "passive"))
      (node (ref "R17") (pin "1") (pinfunction "1_1") (pintype "passive"))
      (node (ref "R21") (pin "1") (pinfunction "1_1") (pintype "passive"))
      (node (ref "R7") (pin "2") (pinfunction "2_2") (pintype "passive"))
      (node (ref "R9") (pin "1") (pinfunction "1_1") (pintype "passive"))
      (node (ref "RN1") (pin "5") (pinfunction "5_5") (pintype "passive"))
      (node (ref "RN1") (pin "6") (pinfunction "6_6") (pintype "passive"))
      (node (ref "RN1") (pin "7") (pinfunction "7_7") (pintype "passive"))
      (node (ref "RN1") (pin "8") (pinfunction "8_8") (pintype "passive"))
      (node (ref "TP5") (pin "TP") (pinfunction "TP_TP") (pintype "input"))
      (node (ref "U1") (pin "13") (pinfunction "VDDA_13") (pintype "power_in"))
      (node (ref "U1") (pin "14") (pinfunction "VREFH_14") (pintype "power_in"))
      (node (ref "U1") (pin "3") (pinfunction "VDD_3_3") (pintype "power_in"))
      (node (ref "U1") (pin "30") (pinfunction "VDD_2_30") (pintype "power_in"))
      (node (ref "U1") (pin "48") (pinfunction "VDD_48") (pintype "power_in"))
    )
    (net (code "2") (name "+5V") (class "Default")
      (node (ref "C10") (pin "+") (pinfunction "+_+") (pintype "passive"))
      (node (ref "C9") (pin "2") (pinfunction "2_2") (pintype "passive"))
      (node (ref "D2") (pin "C") (pinfunction "C_C") (pintype "passive"))
      (node (ref "D3") (pin "C") (pinfunction "C_C") (pintype "passive"))
      (node (ref "IC4") (pin "3") (pinfunction "VIN_3") (pintype "input"))
      (node (ref "JP5") (pin "3") (pinfunction "3_3") (pintype "passive"))
      (node (ref "R6") (pin "2") (pinfunction "2_2") (pintype "passive"))
      (node (ref "TP4") (pin "TP") (pinfunction "TP_TP") (pintype "input"))
      (node (ref "U1") (pin "8") (pinfunction "VREGIN_8") (pintype "power_in"))
    )
    (net (code "3") (name "+5V_REGLER") (class "Default")
      (node (ref "C7") (pin "2") (pinfunction "2_2") (pintype "passive"))
      (node (ref "C8") (pin "+") (pinfunction "+_+") (pintype "passive"))
      (node (ref "D2") (pin "A") (pinfunction "A_A") (pintype "passive"))
      (node (ref "IC3") (pin "3") (pinfunction "+VOUT_3") (pintype "passive"))
      (node (ref "R5") (pin "2") (pinfunction "2_2") (pintype "passive"))
      (node (ref "TP3") (pin "TP") (pinfunction "TP_TP") (pintype "input"))
    )
    (net (code "4") (name "+5V_USB") (class "Default")
      (node (ref "C1") (pin "2") (pinfunction "2_2") (pintype "passive"))
      (node (ref "C26") (pin "2") (pinfunction "2_2") (pintype "passive"))
      (node (ref "C27") (pin "+") (pinfunction "+_+") (pintype "passive"))
      (node (ref "C29") (pin "2") (pinfunction "2_2") (pintype "passive"))
      (node (ref "IC1") (pin "5") (pinfunction "P$5_5") (pintype "bidirectional"))
      (node (ref "IC5") (pin "1") (pinfunction "VCCIO_1") (pintype "power_in"))
      (node (ref "IC5") (pin "19") (pinfunction "VCC_19") (pintype "power_in"))
      (node (ref "L1") (pin "3") (pinfunction "3_3") (pintype "passive"))
      (node (ref "OC1") (pin "1") (pinfunction "A_1") (pintype "passive"))
      (node (ref "OC2") (pin "6") (pinfunction "VCC_6") (pintype "bidirectional"))
      (node (ref "R10") (pin "2") (pinfunction "2_2") (pintype "passive"))
      (node (ref "R11") (pin "1") (pinfunction "1_1") (pintype "passive"))
      (node (ref "R12") (pin "2") (pinfunction "2_2") (pintype "passive"))
      (node (ref "R13") (pin "2") (pinfunction "2_2") (pintype "passive"))
      (node (ref "R22") (pin "1") (pinfunction "1_1") (pintype "passive"))
      (node (ref "TP8") (pin "TP") (pinfunction "TP_TP") (pintype "input"))
    )
    (net (code "5") (name "+5V_USB_SUP") (class "Default")
      (node (ref "C2") (pin "2") (pinfunction "2_2") (pintype "passive"))
      (node (ref "D3") (pin "A") (pinfunction "A_A") (pintype "passive"))
      (node (ref "IC2") (pin "5") (pinfunction "P$5_5") (pintype "bidirectional"))
      (node (ref "L2") (pin "3") (pinfunction "3_3") (pintype "passive"))
      (node (ref "R4") (pin "2") (pinfunction "2_2") (pintype "passive"))
      (node (ref "TP2") (pin "TP") (pinfunction "TP_TP") (pintype "input"))
    )
    (net (code "6") (name "+12V") (class "Default")
      (node (ref "C3") (pin "2") (pinfunction "2_2") (pintype "passive"))
      (node (ref "C4") (pin "1") (pinfunction "1_1") (pintype "passive"))
      (node (ref "C40") (pin "2") (pinfunction "2_2") (pintype "passive"))
      (node (ref "C44") (pin "2") (pinfunction "2_2") (pintype "passive"))
      (node (ref "C48") (pin "2") (pinfunction "2_2") (pintype "passive"))
      (node (ref "C5") (pin "2") (pinfunction "2_2") (pintype "passive"))
      (node (ref "C52") (pin "2") (pinfunction "2_2") (pintype "passive"))
      (node (ref "C56") (pin "2") (pinfunction "2_2") (pintype "passive"))
      (node (ref "C6") (pin "1") (pinfunction "1_1") (pintype "passive"))
      (node (ref "C60") (pin "2") (pinfunction "2_2") (pintype "passive"))
      (node (ref "C64") (pin "2") (pinfunction "2_2") (pintype "passive"))
      (node (ref "C68") (pin "2") (pinfunction "2_2") (pintype "passive"))
      (node (ref "C72") (pin "2") (pinfunction "2_2") (pintype "passive"))
      (node (ref "C76") (pin "2") (pinfunction "2_2") (pintype "passive"))
      (node (ref "D1") (pin "C") (pinfunction "C_C") (pintype "passive"))
      (node (ref "D20") (pin "3") (pinfunction "C_3") (pintype "passive"))
      (node (ref "D25") (pin "3") (pinfunction "C_3") (pintype "passive"))
      (node (ref "D30") (pin "3") (pinfunction "C_3") (pintype "passive"))
      (node (ref "D35") (pin "3") (pinfunction "C_3") (pintype "passive"))
      (node (ref "D40") (pin "3") (pinfunction "C_3") (pintype "passive"))
      (node (ref "D45") (pin "3") (pinfunction "C_3") (pintype "passive"))
      (node (ref "D50") (pin "3") (pinfunction "C_3") (pintype "passive"))
      (node (ref "D55") (pin "3") (pinfunction "C_3") (pintype "passive"))
      (node (ref "D60") (pin "3") (pinfunction "C_3") (pintype "passive"))
      (node (ref "D67") (pin "3") (pinfunction "C_3") (pintype "passive"))
      (node (ref "IC10") (pin "5") (pinfunction "VIN_5") (pintype "bidirectional"))
      (node (ref "IC11") (pin "5") (pinfunction "VIN_5") (pintype "bidirectional"))
      (node (ref "IC12") (pin "5") (pinfunction "VIN_5") (pintype "bidirectional"))
      (node (ref "IC13") (pin "5") (pinfunction "VIN_5") (pintype "bidirectional"))
      (node (ref "IC14") (pin "5") (pinfunction "VIN_5") (pintype "bidirectional"))
      (node (ref "IC15") (pin "5") (pinfunction "VIN_5") (pintype "bidirectional"))
      (node (ref "IC16") (pin "5") (pinfunction "VIN_5") (pintype "bidirectional"))
      (node (ref "IC17") (pin "5") (pinfunction "VIN_5") (pintype "bidirectional"))
      (node (ref "IC18") (pin "5") (pinfunction "VIN_5") (pintype "bidirectional"))
      (node (ref "IC19") (pin "5") (pinfunction "VIN_5") (pintype "bidirectional"))
      (node (ref "IC3") (pin "1") (pinfunction "+VIN_1") (pintype "passive"))
      (node (ref "R3") (pin "2") (pinfunction "2_2") (pintype "passive"))
      (node (ref "TP1") (pin "TP") (pinfunction "TP_TP") (pintype "input"))
    )
    (net (code "7") (name "CODE_0") (class "Default")
      (node (ref "JP3") (pin "7") (pinfunction "7_7") (pintype "passive"))
      (node (ref "RN1") (pin "1") (pinfunction "1_1") (pintype "passive"))
      (node (ref "U1") (pin "53") (pinfunction "PTC8_53") (pintype "bidirectional"))
    )
    (net (code "8") (name "CODE_1") (class "Default")
      (node (ref "JP3") (pin "5") (pinfunction "5_5") (pintype "passive"))
      (node (ref "RN1") (pin "2") (pinfunction "2_2") (pintype "passive"))
      (node (ref "U1") (pin "54") (pinfunction "PTC9_54") (pintype "bidirectional"))
    )
    (net (code "9") (name "CODE_2") (class "Default")
      (node (ref "JP3") (pin "3") (pinfunction "3_3") (pintype "passive"))
      (node (ref "RN1") (pin "3") (pinfunction "3_3") (pintype "passive"))
      (node (ref "U1") (pin "55") (pinfunction "PTC10_55") (pintype "bidirectional"))
    )
    (net (code "10") (name "CODE_3") (class "Default")
      (node (ref "JP3") (pin "1") (pinfunction "1_1") (pintype "passive"))
      (node (ref "RN1") (pin "4") (pinfunction "4_4") (pintype "passive"))
      (node (ref "U1") (pin "56") (pinfunction "PTC11_56") (pintype "bidirectional"))
    )
    (net (code "11") (name "GND") (class "Default")
      (node (ref "C10") (pin "-") (pinfunction "-_-") (pintype "passive"))
      (node (ref "C11") (pin "1") (pinfunction "1_1") (pintype "passive"))
      (node (ref "C12") (pin "-") (pinfunction "-_-") (pintype "passive"))
      (node (ref "C13") (pin "1") (pinfunction "1_1") (pintype "passive"))
      (node (ref "C2") (pin "1") (pinfunction "1_1") (pintype "passive"))
      (node (ref "C20") (pin "-") (pinfunction "-_-") (pintype "passive"))
      (node (ref "C21") (pin "1") (pinfunction "1_1") (pintype "passive"))
      (node (ref "C22") (pin "2") (pinfunction "2_2") (pintype "passive"))
      (node (ref "C23") (pin "2") (pinfunction "2_2") (pintype "passive"))
      (node (ref "C24") (pin "2") (pinfunction "2_2") (pintype "passive"))
      (node (ref "C25") (pin "1") (pinfunction "1_1") (pintype "passive"))
      (node (ref "C3") (pin "1") (pinfunction "1_1") (pintype "passive"))
      (node (ref "C4") (pin "2") (pinfunction "2_2") (pintype "passive"))
      (node (ref "C40") (pin "1") (pinfunction "1_1") (pintype "passive"))
      (node (ref "C42") (pin "1") (pinfunction "1_1") (pintype "passive"))
      (node (ref "C44") (pin "1") (pinfunction "1_1") (pintype "passive"))
      (node (ref "C46") (pin "1") (pinfunction "1_1") (pintype "passive"))
      (node (ref "C48") (pin "1") (pinfunction "1_1") (pintype "passive"))
      (node (ref "C5") (pin "1") (pinfunction "1_1") (pintype "passive"))
      (node (ref "C50") (pin "1") (pinfunction "1_1") (pintype "passive"))
      (node (ref "C52") (pin "1") (pinfunction "1_1") (pintype "passive"))
      (node (ref "C54") (pin "1") (pinfunction "1_1") (pintype "passive"))
      (node (ref "C56") (pin "1") (pinfunction "1_1") (pintype "passive"))
      (node (ref "C58") (pin "1") (pinfunction "1_1") (pintype "passive"))
      (node (ref "C6") (pin "2") (pinfunction "2_2") (pintype "passive"))
      (node (ref "C60") (pin "1") (pinfunction "1_1") (pintype "passive"))
      (node (ref "C62") (pin "1") (pinfunction "1_1") (pintype "passive"))
      (node (ref "C64") (pin "1") (pinfunction "1_1") (pintype "passive"))
      (node (ref "C66") (pin "1") (pinfunction "1_1") (pintype "passive"))
      (node (ref "C68") (pin "1") (pinfunction "1_1") (pintype "passive"))
      (node (ref "C7") (pin "1") (pinfunction "1_1") (pintype "passive"))
      (node (ref "C70") (pin "1") (pinfunction "1_1") (pintype "passive"))
      (node (ref "C72") (pin "1") (pinfunction "1_1") (pintype "passive"))
      (node (ref "C74") (pin "1") (pinfunction "1_1") (pintype "passive"))
      (node (ref "C76") (pin "1") (pinfunction "1_1") (pintype "passive"))
      (node (ref "C78") (pin "1") (pinfunction "1_1") (pintype "passive"))
      (node (ref "C8") (pin "-") (pinfunction "-_-") (pintype "passive"))
      (node (ref "C9") (pin "1") (pinfunction "1_1") (pintype "passive"))
      (node (ref "D22") (pin "A") (pinfunction "A_A") (pintype "passive"))
      (node (ref "D27") (pin "A") (pinfunction "A_A") (pintype "passive"))
      (node (ref "D32") (pin "A") (pinfunction "A_A") (pintype "passive"))
      (node (ref "D37") (pin "A") (pinfunction "A_A") (pintype "passive"))
      (node (ref "D4") (pin "C") (pinfunction "C_C") (pintype "passive"))
      (node (ref "D42") (pin "A") (pinfunction "A_A") (pintype "passive"))
      (node (ref "D47") (pin "A") (pinfunction "A_A") (pintype "passive"))
      (node (ref "D5") (pin "C") (pinfunction "C_C") (pintype "passive"))
      (node (ref "D52") (pin "A") (pinfunction "A_A") (pintype "passive"))
      (node (ref "D57") (pin "A") (pinfunction "A_A") (pintype "passive"))
      (node (ref "D6") (pin "C") (pinfunction "C_C") (pintype "passive"))
      (node (ref "D62") (pin "A") (pinfunction "A_A") (pintype "passive"))
      (node (ref "D69") (pin "A") (pinfunction "A_A") (pintype "passive"))
      (node (ref "D7") (pin "C") (pinfunction "C_C") (pintype "passive"))
      (node (ref "D8") (pin "C") (pinfunction "C_C") (pintype "passive"))
      (node (ref "IC10") (pin "2") (pinfunction "GND_2") (pintype "bidirectional"))
      (node (ref "IC11") (pin "2") (pinfunction "GND_2") (pintype "bidirectional"))
      (node (ref "IC12") (pin "2") (pinfunction "GND_2") (pintype "bidirectional"))
      (node (ref "IC13") (pin "2") (pinfunction "GND_2") (pintype "bidirectional"))
      (node (ref "IC14") (pin "2") (pinfunction "GND_2") (pintype "bidirectional"))
      (node (ref "IC15") (pin "2") (pinfunction "GND_2") (pintype "bidirectional"))
      (node (ref "IC16") (pin "2") (pinfunction "GND_2") (pintype "bidirectional"))
      (node (ref "IC17") (pin "2") (pinfunction "GND_2") (pintype "bidirectional"))
      (node (ref "IC18") (pin "2") (pinfunction "GND_2") (pintype "bidirectional"))
      (node (ref "IC19") (pin "2") (pinfunction "GND_2") (pintype "bidirectional"))
      (node (ref "IC2") (pin "2") (pinfunction "P$2_2") (pintype "bidirectional"))
      (node (ref "IC3") (pin "2") (pinfunction "GND_2") (pintype "passive"))
      (node (ref "IC4") (pin "1") (pinfunction "GND_1") (pintype "power_in"))
      (node (ref "JP19") (pin "1") (pinfunction "1_1") (pintype "passive"))
      (node (ref "JP2") (pin "3") (pinfunction "3_3") (pintype "passive"))
      (node (ref "JP3") (pin "2") (pinfunction "2_2") (pintype "passive"))
      (node (ref "JP3") (pin "4") (pinfunction "4_4") (pintype "passive"))
      (node (ref "JP3") (pin "6") (pinfunction "6_6") (pintype "passive"))
      (node (ref "JP3") (pin "8") (pinfunction "8_8") (pintype "passive"))
      (node (ref "JP4") (pin "1") (pinfunction "1_1") (pintype "passive"))
      (node (ref "JP6") (pin "10") (pinfunction "10_10") (pintype "passive"))
      (node (ref "JP6") (pin "9") (pinfunction "9_9") (pintype "passive"))
      (node (ref "L2") (pin "2") (pinfunction "2_2") (pintype "passive"))
      (node (ref "OC1") (pin "5") (pinfunction "EMI_5") (pintype "passive"))
      (node (ref "PJ1") (pin "2") (pinfunction "2_2") (pintype "bidirectional"))
      (node (ref "PJ1") (pin "3") (pinfunction "3_3") (pintype "bidirectional"))
      (node (ref "PROG") (pin "3") (pinfunction "3_3") (pintype "passive"))
      (node (ref "PROG") (pin "5") (pinfunction "5_5") (pintype "passive"))
      (node (ref "Q1") (pin "GND1") (pinfunction "GND_GND1") (pintype "power_in"))
      (node (ref "Q1") (pin "GND2") (pinfunction "GND_GND2") (pintype "power_in"))
      (node (ref "R30") (pin "1") (pinfunction "1_1") (pintype "passive"))
      (node (ref "R31") (pin "2") (pinfunction "2_2") (pintype "passive"))
      (node (ref "R32") (pin "1") (pinfunction "1_1") (pintype "passive"))
      (node (ref "R33") (pin "2") (pinfunction "2_2") (pintype "passive"))
      (node (ref "R34") (pin "1") (pinfunction "1_1") (pintype "passive"))
      (node (ref "R35") (pin "2") (pinfunction "2_2") (pintype "passive"))
      (node (ref "R36") (pin "1") (pinfunction "1_1") (pintype "passive"))
      (node (ref "R37") (pin "2") (pinfunction "2_2") (pintype "passive"))
      (node (ref "R38") (pin "1") (pinfunction "1_1") (pintype "passive"))
      (node (ref "R39") (pin "2") (pinfunction "2_2") (pintype "passive"))
      (node (ref "R40") (pin "1") (pinfunction "1_1") (pintype "passive"))
      (node (ref "R41") (pin "2") (pinfunction "2_2") (pintype "passive"))
      (node (ref "R42") (pin "1") (pinfunction "1_1") (pintype "passive"))
      (node (ref "R43") (pin "2") (pinfunction "2_2") (pintype "passive"))
      (node (ref "R44") (pin "1") (pinfunction "1_1") (pintype "passive"))
      (node (ref "R45") (pin "2") (pinfunction "2_2") (pintype "passive"))
      (node (ref "R46") (pin "1") (pinfunction "1_1") (pintype "passive"))
      (node (ref "R47") (pin "2") (pinfunction "2_2") (pintype "passive"))
      (node (ref "R48") (pin "1") (pinfunction "1_1") (pintype "passive"))
      (node (ref "R49") (pin "2") (pinfunction "2_2") (pintype "passive"))
      (node (ref "TP6") (pin "TP") (pinfunction "TP_TP") (pintype "input"))
      (node (ref "U1") (pin "15") (pinfunction "VREFL_15") (pintype "power_in"))
      (node (ref "U1") (pin "16") (pinfunction "VSSA_16") (pintype "power_in"))
      (node (ref "U1") (pin "31") (pinfunction "VSS_3_31") (pintype "power_in"))
      (node (ref "U1") (pin "4") (pinfunction "VSS_2_4") (pintype "power_in"))
      (node (ref "U1") (pin "47") (pinfunction "VSS_47") (pintype "power_in"))
      (node (ref "X2") (pin "5") (pinfunction "GND_5") (pintype "passive"))
      (node (ref "X2") (pin "GND1") (pinfunction "S1_GND1") (pintype "passive"))
      (node (ref "X2") (pin "GND2") (pinfunction "S2_GND2") (pintype "passive"))
      (node (ref "X2") (pin "GND3") (pinfunction "S3_GND3") (pintype "passive"))
      (node (ref "X2") (pin "GND4") (pinfunction "S4_GND4") (pintype "passive"))
    )
    (net (code "12") (name "GND-USB") (class "Default")
      (node (ref "C1") (pin "1") (pinfunction "1_1") (pintype "passive"))
      (node (ref "C26") (pin "1") (pinfunction "1_1") (pintype "passive"))
      (node (ref "C27") (pin "-") (pinfunction "-_-") (pintype "passive"))
      (node (ref "C28") (pin "1") (pinfunction "1_1") (pintype "passive"))
      (node (ref "C29") (pin "1") (pinfunction "1_1") (pintype "passive"))
      (node (ref "IC1") (pin "2") (pinfunction "P$2_2") (pintype "bidirectional"))
      (node (ref "IC5") (pin "17") (pinfunction "GND_17") (pintype "power_in"))
      (node (ref "IC5") (pin "20") (pinfunction "GND_20") (pintype "power_in"))
      (node (ref "IC5") (pin "24") (pinfunction "GND_24") (pintype "power_in"))
      (node (ref "IC5") (pin "26") (pinfunction "TEST_26") (pintype "input"))
      (node (ref "IC5") (pin "4") (pinfunction "GND_4") (pintype "power_in"))
      (node (ref "JP19") (pin "2") (pinfunction "2_2") (pintype "passive"))
      (node (ref "L1") (pin "2") (pinfunction "2_2") (pintype "passive"))
      (node (ref "OC2") (pin "5") (pinfunction "EMI_5") (pintype "passive"))
      (node (ref "TP7") (pin "TP") (pinfunction "TP_TP") (pintype "input"))
      (node (ref "X1") (pin "5") (pinfunction "GND_5") (pintype "passive"))
      (node (ref "X1") (pin "GND1") (pinfunction "S1_GND1") (pintype "passive"))
      (node (ref "X1") (pin "GND2") (pinfunction "S2_GND2") (pintype "passive"))
      (node (ref "X1") (pin "GND3") (pinfunction "S3_GND3") (pintype "passive"))
      (node (ref "X1") (pin "GND4") (pinfunction "S4_GND4") (pintype "passive"))
    )
    (net (code "13") (name "LED0") (class "Default")
      (node (ref "D11") (pin "C") (pinfunction "C_C") (pintype "passive"))
      (node (ref "JP8") (pin "1") (pinfunction "1_1") (pintype "passive"))
      (node (ref "U1") (pin "42") (pinfunction "PTB19_42") (pintype "bidirectional"))
    )
    (net (code "14") (name "LED1") (class "Default")
      (node (ref "D12") (pin "C") (pinfunction "C_C") (pintype "passive"))
      (node (ref "JP8") (pin "2") (pinfunction "2_2") (pintype "passive"))
      (node (ref "U1") (pin "41") (pinfunction "PTB18_41") (pintype "bidirectional"))
    )
    (net (code "15") (name "LED2") (class "Default")
      (node (ref "D13") (pin "C") (pinfunction "C_C") (pintype "passive"))
      (node (ref "JP8") (pin "3") (pinfunction "3_3") (pintype "passive"))
      (node (ref "U1") (pin "40") (pinfunction "PTB17_40") (pintype "bidirectional"))
    )
    (net (code "16") (name "MCU_UART1_RXD") (class "Default")
      (node (ref "JP1") (pin "3") (pinfunction "3_3") (pintype "passive"))
      (node (ref "OC1") (pin "4") (pinfunction "COL_4") (pintype "passive"))
      (node (ref "R21") (pin "2") (pinfunction "2_2") (pintype "passive"))
    )
    (net (code "17") (name "MCU_UART1_TXD") (class "Default")
      (node (ref "JP1") (pin "1") (pinfunction "1_1") (pintype "passive"))
      (node (ref "R24") (pin "1") (pinfunction "1_1") (pintype "passive"))
    )
    (net (code "18") (name "MCU_UART2_RXD") (class "Default")
      (node (ref "JP2") (pin "2") (pinfunction "2_2") (pintype "passive"))
      (node (ref "U1") (pin "59") (pinfunction "PTD2_59") (pintype "bidirectional"))
    )
    (net (code "19") (name "MCU_UART2_TXD") (class "Default")
      (node (ref "JP2") (pin "1") (pinfunction "1_1") (pintype "passive"))
      (node (ref "U1") (pin "60") (pinfunction "PTD3_60") (pintype "bidirectional"))
    )
    (net (code "20") (name "NMI") (class "Default")
      (node (ref "R9") (pin "2") (pinfunction "2_2") (pintype "passive"))
      (node (ref "U1") (pin "26") (pinfunction "PTA4_26") (pintype "bidirectional"))
    )
    (net (code "21") (name "Net-(C42-Pad2)") (class "Default")
      (node (ref "C42") (pin "2") (pinfunction "2_2") (pintype "passive"))
      (node (ref "C43") (pin "1") (pinfunction "1_1") (pintype "passive"))
      (node (ref "D23") (pin "A") (pinfunction "A_A") (pintype "passive"))
      (node (ref "L20") (pin "2") (pinfunction "2_2") (pintype "passive"))
    )
    (net (code "22") (name "Net-(C46-Pad2)") (class "Default")
      (node (ref "C46") (pin "2") (pinfunction "2_2") (pintype "passive"))
      (node (ref "C47") (pin "1") (pinfunction "1_1") (pintype "passive"))
      (node (ref "D28") (pin "A") (pinfunction "A_A") (pintype "passive"))
      (node (ref "L21") (pin "2") (pinfunction "2_2") (pintype "passive"))
    )
    (net (code "23") (name "Net-(C50-Pad2)") (class "Default")
      (node (ref "C50") (pin "2") (pinfunction "2_2") (pintype "passive"))
      (node (ref "C51") (pin "1") (pinfunction "1_1") (pintype "passive"))
      (node (ref "D33") (pin "A") (pinfunction "A_A") (pintype "passive"))
      (node (ref "L22") (pin "2") (pinfunction "2_2") (pintype "passive"))
    )
    (net (code "24") (name "Net-(C54-Pad2)") (class "Default")
      (node (ref "C54") (pin "2") (pinfunction "2_2") (pintype "passive"))
      (node (ref "C55") (pin "1") (pinfunction "1_1") (pintype "passive"))
      (node (ref "D38") (pin "A") (pinfunction "A_A") (pintype "passive"))
      (node (ref "L23") (pin "2") (pinfunction "2_2") (pintype "passive"))
    )
    (net (code "25") (name "Net-(C58-Pad2)") (class "Default")
      (node (ref "C58") (pin "2") (pinfunction "2_2") (pintype "passive"))
      (node (ref "C59") (pin "1") (pinfunction "1_1") (pintype "passive"))
      (node (ref "D43") (pin "A") (pinfunction "A_A") (pintype "passive"))
      (node (ref "L24") (pin "2") (pinfunction "2_2") (pintype "passive"))
    )
    (net (code "26") (name "Net-(C62-Pad2)") (class "Default")
      (node (ref "C62") (pin "2") (pinfunction "2_2") (pintype "passive"))
      (node (ref "C63") (pin "1") (pinfunction "1_1") (pintype "passive"))
      (node (ref "D48") (pin "A") (pinfunction "A_A") (pintype "passive"))
      (node (ref "L25") (pin "2") (pinfunction "2_2") (pintype "passive"))
    )
    (net (code "27") (name "Net-(C66-Pad2)") (class "Default")
      (node (ref "C66") (pin "2") (pinfunction "2_2") (pintype "passive"))
      (node (ref "C67") (pin "1") (pinfunction "1_1") (pintype "passive"))
      (node (ref "D53") (pin "A") (pinfunction "A_A") (pintype "passive"))
      (node (ref "L26") (pin "2") (pinfunction "2_2") (pintype "passive"))
    )
    (net (code "28") (name "Net-(C70-Pad2)") (class "Default")
      (node (ref "C70") (pin "2") (pinfunction "2_2") (pintype "passive"))
      (node (ref "C71") (pin "1") (pinfunction "1_1") (pintype "passive"))
      (node (ref "D58") (pin "A") (pinfunction "A_A") (pintype "passive"))
      (node (ref "L27") (pin "2") (pinfunction "2_2") (pintype "passive"))
    )
    (net (code "29") (name "Net-(C74-Pad2)") (class "Default")
      (node (ref "C74") (pin "2") (pinfunction "2_2") (pintype "passive"))
      (node (ref "C75") (pin "1") (pinfunction "1_1") (pintype "passive"))
      (node (ref "D63") (pin "A") (pinfunction "A_A") (pintype "passive"))
      (node (ref "L28") (pin "2") (pinfunction "2_2") (pintype "passive"))
    )
    (net (code "30") (name "Net-(C78-Pad2)") (class "Default")
      (node (ref "C78") (pin "2") (pinfunction "2_2") (pintype "passive"))
      (node (ref "C79") (pin "1") (pinfunction "1_1") (pintype "passive"))
      (node (ref "D70") (pin "A") (pinfunction "A_A") (pintype "passive"))
      (node (ref "L29") (pin "2") (pinfunction "2_2") (pintype "passive"))
    )
    (net (code "31") (name "Net-(D1-A-PadA1)") (class "Default")
      (node (ref "D1") (pin "A1") (pinfunction "A_A1") (pintype "passive"))
      (node (ref "D1") (pin "A2") (pinfunction "A_A2") (pintype "passive"))
      (node (ref "PJ1") (pin "1.1") (pinfunction "1_1.1") (pintype "bidirectional"))
      (node (ref "PJ1") (pin "1.2") (pinfunction "1_1.2") (pintype "bidirectional"))
    )
    (net (code "32") (name "Net-(D4-PadA)") (class "Default")
      (node (ref "D4") (pin "A") (pinfunction "A_A") (pintype "passive"))
      (node (ref "R3") (pin "1") (pinfunction "1_1") (pintype "passive"))
    )
    (net (code "33") (name "Net-(D5-PadA)") (class "Default")
      (node (ref "D5") (pin "A") (pinfunction "A_A") (pintype "passive"))
      (node (ref "R4") (pin "1") (pinfunction "1_1") (pintype "passive"))
    )
    (net (code "34") (name "Net-(D6-PadA)") (class "Default")
      (node (ref "D6") (pin "A") (pinfunction "A_A") (pintype "passive"))
      (node (ref "R5") (pin "1") (pinfunction "1_1") (pintype "passive"))
    )
    (net (code "35") (name "Net-(D7-PadA)") (class "Default")
      (node (ref "D7") (pin "A") (pinfunction "A_A") (pintype "passive"))
      (node (ref "R6") (pin "1") (pinfunction "1_1") (pintype "passive"))
    )
    (net (code "36") (name "Net-(D8-PadA)") (class "Default")
      (node (ref "D8") (pin "A") (pinfunction "A_A") (pintype "passive"))
      (node (ref "R7") (pin "1") (pinfunction "1_1") (pintype "passive"))
    )
    (net (code "37") (name "Net-(D9-PadA)") (class "Default")
      (node (ref "D9") (pin "A") (pinfunction "A_A") (pintype "passive"))
      (node (ref "R11") (pin "2") (pinfunction "2_2") (pintype "passive"))
    )
    (net (code "38") (name "Net-(D10-PadA)") (class "Default")
      (node (ref "D10") (pin "A") (pinfunction "A_A") (pintype "passive"))
      (node (ref "R12") (pin "1") (pinfunction "1_1") (pintype "passive"))
    )
    (net (code "39") (name "Net-(D11-PadA)") (class "Default")
      (node (ref "D11") (pin "A") (pinfunction "A_A") (pintype "passive"))
      (node (ref "R14") (pin "1") (pinfunction "1_1") (pintype "passive"))
    )
    (net (code "40") (name "Net-(D12-PadA)") (class "Default")
      (node (ref "D12") (pin "A") (pinfunction "A_A") (pintype "passive"))
      (node (ref "R15") (pin "1") (pinfunction "1_1") (pintype "passive"))
    )
    (net (code "41") (name "Net-(D13-PadA)") (class "Default")
      (node (ref "D13") (pin "A") (pinfunction "A_A") (pintype "passive"))
      (node (ref "R16") (pin "1") (pinfunction "1_1") (pintype "passive"))
    )
    (net (code "42") (name "Net-(D20-A)") (class "Default")
      (node (ref "D20") (pin "1") (pinfunction "A_1") (pintype "passive"))
      (node (ref "D21") (pin "A") (pinfunction "A_A") (pintype "passive"))
    )
    (net (code "43") (name "Net-(D23-PadC)") (class "Default")
      (node (ref "D23") (pin "C") (pinfunction "C_C") (pintype "passive"))
      (node (ref "D24") (pin "A") (pinfunction "A_A") (pintype "passive"))
    )
    (net (code "44") (name "Net-(D25-A)") (class "Default")
      (node (ref "D25") (pin "1") (pinfunction "A_1") (pintype "passive"))
      (node (ref "D26") (pin "A") (pinfunction "A_A") (pintype "passive"))
    )
    (net (code "45") (name "Net-(D28-PadC)") (class "Default")
      (node (ref "D28") (pin "C") (pinfunction "C_C") (pintype "passive"))
      (node (ref "D29") (pin "A") (pinfunction "A_A") (pintype "passive"))
    )
    (net (code "46") (name "Net-(D30-A)") (class "Default")
      (node (ref "D30") (pin "1") (pinfunction "A_1") (pintype "passive"))
      (node (ref "D31") (pin "A") (pinfunction "A_A") (pintype "passive"))
    )
    (net (code "47") (name "Net-(D33-PadC)") (class "Default")
      (node (ref "D33") (pin "C") (pinfunction "C_C") (pintype "passive"))
      (node (ref "D34") (pin "A") (pinfunction "A_A") (pintype "passive"))
    )
    (net (code "48") (name "Net-(D35-A)") (class "Default")
      (node (ref "D35") (pin "1") (pinfunction "A_1") (pintype "passive"))
      (node (ref "D36") (pin "A") (pinfunction "A_A") (pintype "passive"))
    )
    (net (code "49") (name "Net-(D38-PadC)") (class "Default")
      (node (ref "D38") (pin "C") (pinfunction "C_C") (pintype "passive"))
      (node (ref "D39") (pin "A") (pinfunction "A_A") (pintype "passive"))
    )
    (net (code "50") (name "Net-(D40-A)") (class "Default")
      (node (ref "D40") (pin "1") (pinfunction "A_1") (pintype "passive"))
      (node (ref "D41") (pin "A") (pinfunction "A_A") (pintype "passive"))
    )
    (net (code "51") (name "Net-(D43-PadC)") (class "Default")
      (node (ref "D43") (pin "C") (pinfunction "C_C") (pintype "passive"))
      (node (ref "D44") (pin "A") (pinfunction "A_A") (pintype "passive"))
    )
    (net (code "52") (name "Net-(D45-A)") (class "Default")
      (node (ref "D45") (pin "1") (pinfunction "A_1") (pintype "passive"))
      (node (ref "D46") (pin "A") (pinfunction "A_A") (pintype "passive"))
    )
    (net (code "53") (name "Net-(D48-PadC)") (class "Default")
      (node (ref "D48") (pin "C") (pinfunction "C_C") (pintype "passive"))
      (node (ref "D49") (pin "A") (pinfunction "A_A") (pintype "passive"))
    )
    (net (code "54") (name "Net-(D50-A)") (class "Default")
      (node (ref "D50") (pin "1") (pinfunction "A_1") (pintype "passive"))
      (node (ref "D51") (pin "A") (pinfunction "A_A") (pintype "passive"))
    )
    (net (code "55") (name "Net-(D53-PadC)") (class "Default")
      (node (ref "D53") (pin "C") (pinfunction "C_C") (pintype "passive"))
      (node (ref "D54") (pin "A") (pinfunction "A_A") (pintype "passive"))
    )
    (net (code "56") (name "Net-(D55-A)") (class "Default")
      (node (ref "D55") (pin "1") (pinfunction "A_1") (pintype "passive"))
      (node (ref "D56") (pin "A") (pinfunction "A_A") (pintype "passive"))
    )
    (net (code "57") (name "Net-(D58-PadC)") (class "Default")
      (node (ref "D58") (pin "C") (pinfunction "C_C") (pintype "passive"))
      (node (ref "D59") (pin "A") (pinfunction "A_A") (pintype "passive"))
    )
    (net (code "58") (name "Net-(D60-A)") (class "Default")
      (node (ref "D60") (pin "1") (pinfunction "A_1") (pintype "passive"))
      (node (ref "D61") (pin "A") (pinfunction "A_A") (pintype "passive"))
    )
    (net (code "59") (name "Net-(D63-PadC)") (class "Default")
      (node (ref "D63") (pin "C") (pinfunction "C_C") (pintype "passive"))
      (node (ref "D64") (pin "A") (pinfunction "A_A") (pintype "passive"))
    )
    (net (code "60") (name "Net-(D64-PadC)") (class "Default")
      (node (ref "D64") (pin "C") (pinfunction "C_C") (pintype "passive"))
      (node (ref "D65") (pin "A") (pinfunction "A_A") (pintype "passive"))
    )
    (net (code "61") (name "Net-(D65-PadC)") (class "Default")
      (node (ref "D65") (pin "C") (pinfunction "C_C") (pintype "passive"))
      (node (ref "D66") (pin "A") (pinfunction "A_A") (pintype "passive"))
    )
    (net (code "62") (name "Net-(D67-A)") (class "Default")
      (node (ref "D67") (pin "1") (pinfunction "A_1") (pintype "passive"))
      (node (ref "D68") (pin "A") (pinfunction "A_A") (pintype "passive"))
    )
    (net (code "63") (name "Net-(D70-PadC)") (class "Default")
      (node (ref "D70") (pin "C") (pinfunction "C_C") (pintype "passive"))
      (node (ref "D71") (pin "A") (pinfunction "A_A") (pintype "passive"))
    )
    (net (code "64") (name "Net-(D71-PadC)") (class "Default")
      (node (ref "D71") (pin "C") (pinfunction "C_C") (pintype "passive"))
      (node (ref "D72") (pin "A") (pinfunction "A_A") (pintype "passive"))
    )
    (net (code "65") (name "Net-(D72-PadC)") (class "Default")
      (node (ref "D72") (pin "C") (pinfunction "C_C") (pintype "passive"))
      (node (ref "D73") (pin "A") (pinfunction "A_A") (pintype "passive"))
    )
    (net (code "66") (name "Net-(IC1-P$1)") (class "Default")
      (node (ref "IC1") (pin "1") (pinfunction "P$1_1") (pintype "bidirectional"))
      (node (ref "X1") (pin "2") (pinfunction "D-_2") (pintype "passive"))
    )
    (net (code "67") (name "Net-(IC1-P$3)") (class "Default")
      (node (ref "IC1") (pin "3") (pinfunction "P$3_3") (pintype "bidirectional"))
      (node (ref "X1") (pin "3") (pinfunction "D+_3") (pintype "passive"))
    )
    (net (code "68") (name "Net-(IC1-P$4)") (class "Default")
      (node (ref "IC1") (pin "4") (pinfunction "P$4_4") (pintype "bidirectional"))
      (node (ref "IC5") (pin "14") (pinfunction "USBDP_14") (pintype "bidirectional"))
    )
    (net (code "69") (name "Net-(IC1-P$6)") (class "Default")
      (node (ref "IC1") (pin "6") (pinfunction "P$6_6") (pintype "bidirectional"))
      (node (ref "IC5") (pin "15") (pinfunction "USBDM_15") (pintype "bidirectional"))
    )
    (net (code "70") (name "Net-(IC2-P$1)") (class "Default")
      (node (ref "IC2") (pin "1") (pinfunction "P$1_1") (pintype "bidirectional"))
      (node (ref "X2") (pin "2") (pinfunction "D-_2") (pintype "passive"))
    )
    (net (code "71") (name "Net-(IC2-P$3)") (class "Default")
      (node (ref "IC2") (pin "3") (pinfunction "P$3_3") (pintype "bidirectional"))
      (node (ref "X2") (pin "3") (pinfunction "D+_3") (pintype "passive"))
    )
    (net (code "72") (name "Net-(IC2-P$4)") (class "Default")
      (node (ref "IC2") (pin "4") (pinfunction "P$4_4") (pintype "bidirectional"))
      (node (ref "R2") (pin "1") (pinfunction "1_1") (pintype "passive"))
    )
    (net (code "73") (name "Net-(IC2-P$6)") (class "Default")
      (node (ref "IC2") (pin "6") (pinfunction "P$6_6") (pintype "bidirectional"))
      (node (ref "R1") (pin "1") (pinfunction "1_1") (pintype "passive"))
    )
    (net (code "74") (name "Net-(IC5-3V3OUT)") (class "Default")
      (node (ref "C28") (pin "2") (pinfunction "2_2") (pintype "passive"))
      (node (ref "IC5") (pin "16") (pinfunction "3V3OUT_16") (pintype "output"))
    )
    (net (code "75") (name "Net-(IC5-CBUS0)") (class "Default")
      (node (ref "D9") (pin "C") (pinfunction "C_C") (pintype "passive"))
      (node (ref "IC5") (pin "22") (pinfunction "CBUS0_22") (pintype "bidirectional"))
    )
    (net (code "76") (name "Net-(IC5-CBUS1)") (class "Default")
      (node (ref "D10") (pin "C") (pinfunction "C_C") (pintype "passive"))
      (node (ref "IC5") (pin "21") (pinfunction "CBUS1_21") (pintype "bidirectional"))
    )
    (net (code "77") (name "Net-(IC5-CBUS3)") (class "Default")
      (node (ref "IC5") (pin "11") (pinfunction "CBUS3_11") (pintype "bidirectional"))
      (node (ref "R13") (pin "1") (pinfunction "1_1") (pintype "passive"))
    )
    (net (code "78") (name "Net-(IC5-RXD)") (class "Default")
      (node (ref "IC5") (pin "2") (pinfunction "RXD_2") (pintype "input"))
      (node (ref "OC2") (pin "4") (pinfunction "COL_4") (pintype "passive"))
      (node (ref "R22") (pin "2") (pinfunction "2_2") (pintype "passive"))
    )
    (net (code "79") (name "Net-(IC5-TXD)") (class "Default")
      (node (ref "IC5") (pin "30") (pinfunction "TXD_30") (pintype "output"))
      (node (ref "R23") (pin "2") (pinfunction "2_2") (pintype "passive"))
    )
    (net (code "80") (name "Net-(IC5-~{RESET})") (class "Default")
      (node (ref "IC5") (pin "18") (pinfunction "~{RESET}_18") (pintype "input"))
      (node (ref "R10") (pin "1") (pinfunction "1_1") (pintype "passive"))
    )
    (net (code "81") (name "Net-(IC10-BOOST)") (class "Default")
      (node (ref "C41") (pin "1") (pinfunction "1_1") (pintype "passive"))
      (node (ref "D21") (pin "C") (pinfunction "C_C") (pintype "passive"))
      (node (ref "IC10") (pin "1") (pinfunction "BOOST_1") (pintype "bidirectional"))
    )
    (net (code "82") (name "Net-(IC10-EN{slash}DIM)") (class "Default")
      (node (ref "IC10") (pin "4") (pinfunction "EN/DIM_4") (pintype "bidirectional"))
      (node (ref "JP9") (pin "2") (pinfunction "2_2") (pintype "passive"))
      (node (ref "R30") (pin "2") (pinfunction "2_2") (pintype "passive"))
    )
    (net (code "83") (name "Net-(IC10-FB)") (class "Default")
      (node (ref "C43") (pin "2") (pinfunction "2_2") (pintype "passive"))
      (node (ref "D24") (pin "C") (pinfunction "C_C") (pintype "passive"))
      (node (ref "IC10") (pin "3") (pinfunction "FB_3") (pintype "bidirectional"))
      (node (ref "R31") (pin "1") (pinfunction "1_1") (pintype "passive"))
    )
    (net (code "84") (name "Net-(IC10-SW)") (class "Default")
      (node (ref "C41") (pin "2") (pinfunction "2_2") (pintype "passive"))
      (node (ref "D22") (pin "C") (pinfunction "C_C") (pintype "passive"))
      (node (ref "IC10") (pin "6") (pinfunction "SW_6") (pintype "bidirectional"))
      (node (ref "L20") (pin "1") (pinfunction "1_1") (pintype "passive"))
    )
    (net (code "85") (name "Net-(IC11-BOOST)") (class "Default")
      (node (ref "C45") (pin "1") (pinfunction "1_1") (pintype "passive"))
      (node (ref "D26") (pin "C") (pinfunction "C_C") (pintype "passive"))
      (node (ref "IC11") (pin "1") (pinfunction "BOOST_1") (pintype "bidirectional"))
    )
    (net (code "86") (name "Net-(IC11-EN{slash}DIM)") (class "Default")
      (node (ref "IC11") (pin "4") (pinfunction "EN/DIM_4") (pintype "bidirectional"))
      (node (ref "JP10") (pin "2") (pinfunction "2_2") (pintype "passive"))
      (node (ref "R32") (pin "2") (pinfunction "2_2") (pintype "passive"))
    )
    (net (code "87") (name "Net-(IC11-FB)") (class "Default")
      (node (ref "C47") (pin "2") (pinfunction "2_2") (pintype "passive"))
      (node (ref "D29") (pin "C") (pinfunction "C_C") (pintype "passive"))
      (node (ref "IC11") (pin "3") (pinfunction "FB_3") (pintype "bidirectional"))
      (node (ref "R33") (pin "1") (pinfunction "1_1") (pintype "passive"))
    )
    (net (code "88") (name "Net-(IC11-SW)") (class "Default")
      (node (ref "C45") (pin "2") (pinfunction "2_2") (pintype "passive"))
      (node (ref "D27") (pin "C") (pinfunction "C_C") (pintype "passive"))
      (node (ref "IC11") (pin "6") (pinfunction "SW_6") (pintype "bidirectional"))
      (node (ref "L21") (pin "1") (pinfunction "1_1") (pintype "passive"))
    )
    (net (code "89") (name "Net-(IC12-BOOST)") (class "Default")
      (node (ref "C49") (pin "1") (pinfunction "1_1") (pintype "passive"))
      (node (ref "D31") (pin "C") (pinfunction "C_C") (pintype "passive"))
      (node (ref "IC12") (pin "1") (pinfunction "BOOST_1") (pintype "bidirectional"))
    )
    (net (code "90") (name "Net-(IC12-EN{slash}DIM)") (class "Default")
      (node (ref "IC12") (pin "4") (pinfunction "EN/DIM_4") (pintype "bidirectional"))
      (node (ref "JP11") (pin "2") (pinfunction "2_2") (pintype "passive"))
      (node (ref "R34") (pin "2") (pinfunction "2_2") (pintype "passive"))
    )
    (net (code "91") (name "Net-(IC12-FB)") (class "Default")
      (node (ref "C51") (pin "2") (pinfunction "2_2") (pintype "passive"))
      (node (ref "D34") (pin "C") (pinfunction "C_C") (pintype "passive"))
      (node (ref "IC12") (pin "3") (pinfunction "FB_3") (pintype "bidirectional"))
      (node (ref "R35") (pin "1") (pinfunction "1_1") (pintype "passive"))
    )
    (net (code "92") (name "Net-(IC12-SW)") (class "Default")
      (node (ref "C49") (pin "2") (pinfunction "2_2") (pintype "passive"))
      (node (ref "D32") (pin "C") (pinfunction "C_C") (pintype "passive"))
      (node (ref "IC12") (pin "6") (pinfunction "SW_6") (pintype "bidirectional"))
      (node (ref "L22") (pin "1") (pinfunction "1_1") (pintype "passive"))
    )
    (net (code "93") (name "Net-(IC13-BOOST)") (class "Default")
      (node (ref "C53") (pin "1") (pinfunction "1_1") (pintype "passive"))
      (node (ref "D36") (pin "C") (pinfunction "C_C") (pintype "passive"))
      (node (ref "IC13") (pin "1") (pinfunction "BOOST_1") (pintype "bidirectional"))
    )
    (net (code "94") (name "Net-(IC13-EN{slash}DIM)") (class "Default")
      (node (ref "IC13") (pin "4") (pinfunction "EN/DIM_4") (pintype "bidirectional"))
      (node (ref "JP12") (pin "2") (pinfunction "2_2") (pintype "passive"))
      (node (ref "R36") (pin "2") (pinfunction "2_2") (pintype "passive"))
    )
    (net (code "95") (name "Net-(IC13-FB)") (class "Default")
      (node (ref "C55") (pin "2") (pinfunction "2_2") (pintype "passive"))
      (node (ref "D39") (pin "C") (pinfunction "C_C") (pintype "passive"))
      (node (ref "IC13") (pin "3") (pinfunction "FB_3") (pintype "bidirectional"))
      (node (ref "R37") (pin "1") (pinfunction "1_1") (pintype "passive"))
    )
    (net (code "96") (name "Net-(IC13-SW)") (class "Default")
      (node (ref "C53") (pin "2") (pinfunction "2_2") (pintype "passive"))
      (node (ref "D37") (pin "C") (pinfunction "C_C") (pintype "passive"))
      (node (ref "IC13") (pin "6") (pinfunction "SW_6") (pintype "bidirectional"))
      (node (ref "L23") (pin "1") (pinfunction "1_1") (pintype "passive"))
    )
    (net (code "97") (name "Net-(IC14-BOOST)") (class "Default")
      (node (ref "C57") (pin "1") (pinfunction "1_1") (pintype "passive"))
      (node (ref "D41") (pin "C") (pinfunction "C_C") (pintype "passive"))
      (node (ref "IC14") (pin "1") (pinfunction "BOOST_1") (pintype "bidirectional"))
    )
    (net (code "98") (name "Net-(IC14-EN{slash}DIM)") (class "Default")
      (node (ref "IC14") (pin "4") (pinfunction "EN/DIM_4") (pintype "bidirectional"))
      (node (ref "JP13") (pin "2") (pinfunction "2_2") (pintype "passive"))
      (node (ref "R38") (pin "2") (pinfunction "2_2") (pintype "passive"))
    )
    (net (code "99") (name "Net-(IC14-FB)") (class "Default")
      (node (ref "C59") (pin "2") (pinfunction "2_2") (pintype "passive"))
      (node (ref "D44") (pin "C") (pinfunction "C_C") (pintype "passive"))
      (node (ref "IC14") (pin "3") (pinfunction "FB_3") (pintype "bidirectional"))
      (node (ref "R39") (pin "1") (pinfunction "1_1") (pintype "passive"))
    )
    (net (code "100") (name "Net-(IC14-SW)") (class "Default")
      (node (ref "C57") (pin "2") (pinfunction "2_2") (pintype "passive"))
      (node (ref "D42") (pin "C") (pinfunction "C_C") (pintype "passive"))
      (node (ref "IC14") (pin "6") (pinfunction "SW_6") (pintype "bidirectional"))
      (node (ref "L24") (pin "1") (pinfunction "1_1") (pintype "passive"))
    )
    (net (code "101") (name "Net-(IC15-BOOST)") (class "Default")
      (node (ref "C61") (pin "1") (pinfunction "1_1") (pintype "passive"))
      (node (ref "D46") (pin "C") (pinfunction "C_C") (pintype "passive"))
      (node (ref "IC15") (pin "1") (pinfunction "BOOST_1") (pintype "bidirectional"))
    )
    (net (code "102") (name "Net-(IC15-EN{slash}DIM)") (class "Default")
      (node (ref "IC15") (pin "4") (pinfunction "EN/DIM_4") (pintype "bidirectional"))
      (node (ref "JP14") (pin "2") (pinfunction "2_2") (pintype "passive"))
      (node (ref "R40") (pin "2") (pinfunction "2_2") (pintype "passive"))
    )
    (net (code "103") (name "Net-(IC15-FB)") (class "Default")
      (node (ref "C63") (pin "2") (pinfunction "2_2") (pintype "passive"))
      (node (ref "D49") (pin "C") (pinfunction "C_C") (pintype "passive"))
      (node (ref "IC15") (pin "3") (pinfunction "FB_3") (pintype "bidirectional"))
      (node (ref "R41") (pin "1") (pinfunction "1_1") (pintype "passive"))
    )
    (net (code "104") (name "Net-(IC15-SW)") (class "Default")
      (node (ref "C61") (pin "2") (pinfunction "2_2") (pintype "passive"))
      (node (ref "D47") (pin "C") (pinfunction "C_C") (pintype "passive"))
      (node (ref "IC15") (pin "6") (pinfunction "SW_6") (pintype "bidirectional"))
      (node (ref "L25") (pin "1") (pinfunction "1_1") (pintype "passive"))
    )
    (net (code "105") (name "Net-(IC16-BOOST)") (class "Default")
      (node (ref "C65") (pin "1") (pinfunction "1_1") (pintype "passive"))
      (node (ref "D51") (pin "C") (pinfunction "C_C") (pintype "passive"))
      (node (ref "IC16") (pin "1") (pinfunction "BOOST_1") (pintype "bidirectional"))
    )
    (net (code "106") (name "Net-(IC16-EN{slash}DIM)") (class "Default")
      (node (ref "IC16") (pin "4") (pinfunction "EN/DIM_4") (pintype "bidirectional"))
      (node (ref "JP15") (pin "2") (pinfunction "2_2") (pintype "passive"))
      (node (ref "R42") (pin "2") (pinfunction "2_2") (pintype "passive"))
    )
    (net (code "107") (name "Net-(IC16-FB)") (class "Default")
      (node (ref "C67") (pin "2") (pinfunction "2_2") (pintype "passive"))
      (node (ref "D54") (pin "C") (pinfunction "C_C") (pintype "passive"))
      (node (ref "IC16") (pin "3") (pinfunction "FB_3") (pintype "bidirectional"))
      (node (ref "R43") (pin "1") (pinfunction "1_1") (pintype "passive"))
    )
    (net (code "108") (name "Net-(IC16-SW)") (class "Default")
      (node (ref "C65") (pin "2") (pinfunction "2_2") (pintype "passive"))
      (node (ref "D52") (pin "C") (pinfunction "C_C") (pintype "passive"))
      (node (ref "IC16") (pin "6") (pinfunction "SW_6") (pintype "bidirectional"))
      (node (ref "L26") (pin "1") (pinfunction "1_1") (pintype "passive"))
    )
    (net (code "109") (name "Net-(IC17-BOOST)") (class "Default")
      (node (ref "C69") (pin "1") (pinfunction "1_1") (pintype "passive"))
      (node (ref "D56") (pin "C") (pinfunction "C_C") (pintype "passive"))
      (node (ref "IC17") (pin "1") (pinfunction "BOOST_1") (pintype "bidirectional"))
    )
    (net (code "110") (name "Net-(IC17-EN{slash}DIM)") (class "Default")
      (node (ref "IC17") (pin "4") (pinfunction "EN/DIM_4") (pintype "bidirectional"))
      (node (ref "JP16") (pin "2") (pinfunction "2_2") (pintype "passive"))
      (node (ref "R44") (pin "2") (pinfunction "2_2") (pintype "passive"))
    )
    (net (code "111") (name "Net-(IC17-FB)") (class "Default")
      (node (ref "C71") (pin "2") (pinfunction "2_2") (pintype "passive"))
      (node (ref "D59") (pin "C") (pinfunction "C_C") (pintype "passive"))
      (node (ref "IC17") (pin "3") (pinfunction "FB_3") (pintype "bidirectional"))
      (node (ref "R45") (pin "1") (pinfunction "1_1") (pintype "passive"))
    )
    (net (code "112") (name "Net-(IC17-SW)") (class "Default")
      (node (ref "C69") (pin "2") (pinfunction "2_2") (pintype "passive"))
      (node (ref "D57") (pin "C") (pinfunction "C_C") (pintype "passive"))
      (node (ref "IC17") (pin "6") (pinfunction "SW_6") (pintype "bidirectional"))
      (node (ref "L27") (pin "1") (pinfunction "1_1") (pintype "passive"))
    )
    (net (code "113") (name "Net-(IC18-BOOST)") (class "Default")
      (node (ref "C73") (pin "1") (pinfunction "1_1") (pintype "passive"))
      (node (ref "D61") (pin "C") (pinfunction "C_C") (pintype "passive"))
      (node (ref "IC18") (pin "1") (pinfunction "BOOST_1") (pintype "bidirectional"))
    )
    (net (code "114") (name "Net-(IC18-EN{slash}DIM)") (class "Default")
      (node (ref "IC18") (pin "4") (pinfunction "EN/DIM_4") (pintype "bidirectional"))
      (node (ref "JP18") (pin "2") (pinfunction "2_2") (pintype "passive"))
      (node (ref "R46") (pin "2") (pinfunction "2_2") (pintype "passive"))
    )
    (net (code "115") (name "Net-(IC18-FB)") (class "Default")
      (node (ref "C75") (pin "2") (pinfunction "2_2") (pintype "passive"))
      (node (ref "D66") (pin "C") (pinfunction "C_C") (pintype "passive"))
      (node (ref "IC18") (pin "3") (pinfunction "FB_3") (pintype "bidirectional"))
      (node (ref "R47") (pin "1") (pinfunction "1_1") (pintype "passive"))
    )
    (net (code "116") (name "Net-(IC18-SW)") (class "Default")
      (node (ref "C73") (pin "2") (pinfunction "2_2") (pintype "passive"))
      (node (ref "D62") (pin "C") (pinfunction "C_C") (pintype "passive"))
      (node (ref "IC18") (pin "6") (pinfunction "SW_6") (pintype "bidirectional"))
      (node (ref "L28") (pin "1") (pinfunction "1_1") (pintype "passive"))
    )
    (net (code "117") (name "Net-(IC19-BOOST)") (class "Default")
      (node (ref "C77") (pin "1") (pinfunction "1_1") (pintype "passive"))
      (node (ref "D68") (pin "C") (pinfunction "C_C") (pintype "passive"))
      (node (ref "IC19") (pin "1") (pinfunction "BOOST_1") (pintype "bidirectional"))
    )
    (net (code "118") (name "Net-(IC19-EN{slash}DIM)") (class "Default")
      (node (ref "IC19") (pin "4") (pinfunction "EN/DIM_4") (pintype "bidirectional"))
      (node (ref "JP17") (pin "2") (pinfunction "2_2") (pintype "passive"))
      (node (ref "R48") (pin "2") (pinfunction "2_2") (pintype "passive"))
    )
    (net (code "119") (name "Net-(IC19-FB)") (class "Default")
      (node (ref "C79") (pin "2") (pinfunction "2_2") (pintype "passive"))
      (node (ref "D73") (pin "C") (pinfunction "C_C") (pintype "passive"))
      (node (ref "IC19") (pin "3") (pinfunction "FB_3") (pintype "bidirectional"))
      (node (ref "R49") (pin "1") (pinfunction "1_1") (pintype "passive"))
    )
    (net (code "120") (name "Net-(IC19-SW)") (class "Default")
      (node (ref "C77") (pin "2") (pinfunction "2_2") (pintype "passive"))
      (node (ref "D69") (pin "C") (pinfunction "C_C") (pintype "passive"))
      (node (ref "IC19") (pin "6") (pinfunction "SW_6") (pintype "bidirectional"))
      (node (ref "L29") (pin "1") (pinfunction "1_1") (pintype "passive"))
    )
    (net (code "121") (name "Net-(OC1-C)") (class "Default")
      (node (ref "OC1") (pin "3") (pinfunction "C_3") (pintype "passive"))
      (node (ref "R23") (pin "1") (pinfunction "1_1") (pintype "passive"))
    )
    (net (code "122") (name "Net-(OC2-C)") (class "Default")
      (node (ref "OC2") (pin "3") (pinfunction "C_3") (pintype "passive"))
      (node (ref "R24") (pin "2") (pinfunction "2_2") (pintype "passive"))
    )
    (net (code "123") (name "Net-(Q1-2)") (class "Default")
      (node (ref "C24") (pin "1") (pinfunction "1_1") (pintype "passive"))
      (node (ref "Q1") (pin "3") (pinfunction "2_3") (pintype "bidirectional"))
      (node (ref "R8") (pin "1") (pinfunction "1_1") (pintype "passive"))
      (node (ref "U1") (pin "33") (pinfunction "PTA19_33") (pintype "bidirectional"))
    )
    (net (code "124") (name "Net-(U1-PTA18)") (class "Default")
      (node (ref "C23") (pin "1") (pinfunction "1_1") (pintype "passive"))
      (node (ref "Q1") (pin "1") (pinfunction "1_1") (pintype "bidirectional"))
      (node (ref "R8") (pin "2") (pinfunction "2_2") (pintype "passive"))
      (node (ref "U1") (pin "32") (pinfunction "PTA18_32") (pintype "bidirectional"))
    )
    (net (code "125") (name "Net-(U1-PTE0)") (class "Default")
      (node (ref "JP1") (pin "2") (pinfunction "2_2") (pintype "passive"))
      (node (ref "U1") (pin "1") (pinfunction "PTE0_1") (pintype "bidirectional"))
    )
    (net (code "126") (name "Net-(U1-PTE1)") (class "Default")
      (node (ref "JP1") (pin "4") (pinfunction "4_4") (pintype "passive"))
      (node (ref "U1") (pin "2") (pinfunction "PTE1_2") (pintype "bidirectional"))
    )
    (net (code "127") (name "Net-(U1-VOUT33)") (class "Default")
      (node (ref "C22") (pin "1") (pinfunction "1_1") (pintype "passive"))
      (node (ref "U1") (pin "7") (pinfunction "VOUT33_7") (pintype "output"))
    )
    (net (code "128") (name "Net-(X1-VB)") (class "Default")
      (node (ref "L1") (pin "1") (pinfunction "1_1") (pintype "passive"))
      (node (ref "X1") (pin "1") (pinfunction "VB_1") (pintype "passive"))
    )
    (net (code "129") (name "Net-(X2-VB)") (class "Default")
      (node (ref "L2") (pin "1") (pinfunction "1_1") (pintype "passive"))
      (node (ref "X2") (pin "1") (pinfunction "VB_1") (pintype "passive"))
    )
    (net (code "130") (name "PTA5") (class "Default")
      (node (ref "JP5") (pin "4") (pinfunction "4_4") (pintype "passive"))
      (node (ref "U1") (pin "27") (pinfunction "PTA5_27") (pintype "bidirectional"))
    )
    (net (code "131") (name "PTA12") (class "Default")
      (node (ref "JP5") (pin "6") (pinfunction "6_6") (pintype "passive"))
      (node (ref "U1") (pin "28") (pinfunction "PTA12_28") (pintype "bidirectional"))
    )
    (net (code "132") (name "PTA13") (class "Default")
      (node (ref "JP5") (pin "5") (pinfunction "5_5") (pintype "passive"))
      (node (ref "U1") (pin "29") (pinfunction "PTA13_29") (pintype "bidirectional"))
    )
    (net (code "133") (name "PTB0") (class "Default")
      (node (ref "JP8") (pin "8") (pinfunction "8_8") (pintype "passive"))
      (node (ref "U1") (pin "35") (pinfunction "PTB0/LLWU_P5_35") (pintype "bidirectional"))
    )
    (net (code "134") (name "PTB1") (class "Default")
      (node (ref "JP8") (pin "7") (pinfunction "7_7") (pintype "passive"))
      (node (ref "U1") (pin "36") (pinfunction "PTB1_36") (pintype "bidirectional"))
    )
    (net (code "135") (name "PTB2") (class "Default")
      (node (ref "JP8") (pin "6") (pinfunction "6_6") (pintype "passive"))
      (node (ref "U1") (pin "37") (pinfunction "PTB2_37") (pintype "bidirectional"))
    )
    (net (code "136") (name "PTB3") (class "Default")
      (node (ref "JP8") (pin "5") (pinfunction "5_5") (pintype "passive"))
      (node (ref "U1") (pin "38") (pinfunction "PTB3_38") (pintype "bidirectional"))
    )
    (net (code "137") (name "PTB16") (class "Default")
      (node (ref "JP8") (pin "4") (pinfunction "4_4") (pintype "passive"))
      (node (ref "U1") (pin "39") (pinfunction "PTB16_39") (pintype "bidirectional"))
    )
    (net (code "138") (name "PTC0") (class "Default")
      (node (ref "JP7") (pin "8") (pinfunction "8_8") (pintype "passive"))
      (node (ref "U1") (pin "43") (pinfunction "PTC0_43") (pintype "bidirectional"))
    )
    (net (code "139") (name "PTC1") (class "Default")
      (node (ref "JP7") (pin "7") (pinfunction "7_7") (pintype "passive"))
      (node (ref "U1") (pin "44") (pinfunction "PTC1/LLWU_P6/RTC_CLKIN_44") (pintype "bidirectional"))
    )
    (net (code "140") (name "PTC2") (class "Default")
      (node (ref "JP7") (pin "6") (pinfunction "6_6") (pintype "passive"))
      (node (ref "U1") (pin "45") (pinfunction "PTC2_45") (pintype "bidirectional"))
    )
    (net (code "141") (name "PTC3") (class "Default")
      (node (ref "JP7") (pin "5") (pinfunction "5_5") (pintype "passive"))
      (node (ref "U1") (pin "46") (pinfunction "PTC3/LLWU_P7_46") (pintype "bidirectional"))
    )
    (net (code "142") (name "PTC4") (class "Default")
      (node (ref "JP7") (pin "4") (pinfunction "4_4") (pintype "passive"))
      (node (ref "U1") (pin "49") (pinfunction "PTC4/LLWU_P8_49") (pintype "bidirectional"))
    )
    (net (code "143") (name "PTC5") (class "Default")
      (node (ref "JP7") (pin "3") (pinfunction "3_3") (pintype "passive"))
      (node (ref "U1") (pin "50") (pinfunction "PTC5/LLWU_P9_50") (pintype "bidirectional"))
    )
    (net (code "144") (name "PTC6") (class "Default")
      (node (ref "JP7") (pin "2") (pinfunction "2_2") (pintype "passive"))
      (node (ref "U1") (pin "51") (pinfunction "PTC6/LLWU_P10_51") (pintype "bidirectional"))
    )
    (net (code "145") (name "PTC7") (class "Default")
      (node (ref "JP7") (pin "1") (pinfunction "1_1") (pintype "passive"))
      (node (ref "U1") (pin "52") (pinfunction "PTC7_52") (pintype "bidirectional"))
    )
    (net (code "146") (name "PTD0") (class "Default")
      (node (ref "JP6") (pin "6") (pinfunction "6_6") (pintype "passive"))
      (node (ref "U1") (pin "57") (pinfunction "PTD0_57") (pintype "bidirectional"))
    )
    (net (code "147") (name "PTD1") (class "Default")
      (node (ref "JP6") (pin "5") (pinfunction "5_5") (pintype "passive"))
      (node (ref "U1") (pin "58") (pinfunction "PTD1_58") (pintype "bidirectional"))
    )
    (net (code "148") (name "PTD4") (class "Default")
      (node (ref "JP6") (pin "4") (pinfunction "4_4") (pintype "passive"))
      (node (ref "U1") (pin "61") (pinfunction "PTD4/LLWU_P14_61") (pintype "bidirectional"))
    )
    (net (code "149") (name "PTD5") (class "Default")
      (node (ref "JP6") (pin "3") (pinfunction "3_3") (pintype "passive"))
      (node (ref "U1") (pin "62") (pinfunction "PTD5_62") (pintype "bidirectional"))
    )
    (net (code "150") (name "PTD6") (class "Default")
      (node (ref "JP6") (pin "2") (pinfunction "2_2") (pintype "passive"))
      (node (ref "U1") (pin "63") (pinfunction "PTD6/LLWU_P15_63") (pintype "bidirectional"))
    )
    (net (code "151") (name "PTD7") (class "Default")
      (node (ref "JP6") (pin "1") (pinfunction "1_1") (pintype "passive"))
      (node (ref "U1") (pin "64") (pinfunction "PTD7_64") (pintype "bidirectional"))
    )
    (net (code "152") (name "PTE23") (class "Default")
      (node (ref "JP4") (pin "4") (pinfunction "4_4") (pintype "passive"))
      (node (ref "U1") (pin "12") (pinfunction "PTE23_12") (pintype "bidirectional"))
    )
    (net (code "153") (name "PTE24") (class "Default")
      (node (ref "JP5") (pin "2") (pinfunction "2_2") (pintype "passive"))
      (node (ref "U1") (pin "20") (pinfunction "PTE24_20") (pintype "bidirectional"))
    )
    (net (code "154") (name "PTE25") (class "Default")
      (node (ref "JP5") (pin "1") (pinfunction "1_1") (pintype "passive"))
      (node (ref "U1") (pin "21") (pinfunction "PTE25_21") (pintype "bidirectional"))
    )
    (net (code "155") (name "PTE29") (class "Default")
      (node (ref "JP4") (pin "6") (pinfunction "6_6") (pintype "passive"))
      (node (ref "U1") (pin "17") (pinfunction "PTE29_17") (pintype "bidirectional"))
    )
    (net (code "156") (name "PTE30") (class "Default")
      (node (ref "JP4") (pin "3") (pinfunction "3_3") (pintype "passive"))
      (node (ref "U1") (pin "18") (pinfunction "PTE30_18") (pintype "bidirectional"))
    )
    (net (code "157") (name "PTE31") (class "Default")
      (node (ref "JP4") (pin "5") (pinfunction "5_5") (pintype "passive"))
      (node (ref "U1") (pin "19") (pinfunction "PTE31_19") (pintype "bidirectional"))
    )
    (net (code "158") (name "PWM_IR") (class "Default")
      (node (ref "JP17") (pin "1") (pinfunction "1_1") (pintype "passive"))
      (node (ref "JP18") (pin "1") (pinfunction "1_1") (pintype "passive"))
      (node (ref "U1") (pin "11") (pinfunction "PTE22_11") (pintype "bidirectional"))
    )
    (net (code "159") (name "PWM_UV") (class "Default")
      (node (ref "JP10") (pin "1") (pinfunction "1_1") (pintype "passive"))
      (node (ref "JP11") (pin "1") (pinfunction "1_1") (pintype "passive"))
      (node (ref "JP12") (pin "1") (pinfunction "1_1") (pintype "passive"))
      (node (ref "JP9") (pin "1") (pinfunction "1_1") (pintype "passive"))
      (node (ref "U1") (pin "9") (pinfunction "PTE20_9") (pintype "bidirectional"))
    )
    (net (code "160") (name "PWM_WHITE") (class "Default")
      (node (ref "JP13") (pin "1") (pinfunction "1_1") (pintype "passive"))
      (node (ref "JP14") (pin "1") (pinfunction "1_1") (pintype "passive"))
      (node (ref "JP15") (pin "1") (pinfunction "1_1") (pintype "passive"))
      (node (ref "JP16") (pin "1") (pinfunction "1_1") (pintype "passive"))
      (node (ref "U1") (pin "10") (pinfunction "PTE21_10") (pintype "bidirectional"))
    )
    (net (code "161") (name "SWD_CLK_TGTMCU") (class "Default")
      (node (ref "PROG") (pin "4") (pinfunction "4_4") (pintype "passive"))
      (node (ref "U1") (pin "22") (pinfunction "PTA0_22") (pintype "bidirectional"))
    )
    (net (code "162") (name "SWD_DIO_TGTMCU") (class "Default")
      (node (ref "PROG") (pin "2") (pinfunction "2_2") (pintype "passive"))
      (node (ref "U1") (pin "25") (pinfunction "PTA3_25") (pintype "bidirectional"))
    )
    (net (code "163") (name "SWD_RST_TGTMCU") (class "Default")
      (node (ref "C13") (pin "2") (pinfunction "2_2") (pintype "passive"))
      (node (ref "PROG") (pin "10") (pinfunction "10_10") (pintype "passive"))
      (node (ref "R17") (pin "2") (pinfunction "2_2") (pintype "passive"))
      (node (ref "U1") (pin "34") (pinfunction "PTA20_34") (pintype "bidirectional"))
    )
    (net (code "164") (name "USBDM_UART_RX") (class "Default")
      (node (ref "PROG") (pin "7") (pinfunction "7_7") (pintype "passive"))
      (node (ref "U1") (pin "23") (pinfunction "PTA1_23") (pintype "bidirectional"))
    )
    (net (code "165") (name "USBDM_UART_TX") (class "Default")
      (node (ref "PROG") (pin "6") (pinfunction "6_6") (pintype "passive"))
      (node (ref "U1") (pin "24") (pinfunction "PTA2_24") (pintype "bidirectional"))
    )
    (net (code "166") (name "USB_DM_TGTMCU") (class "Default")
      (node (ref "R1") (pin "2") (pinfunction "2_2") (pintype "passive"))
      (node (ref "U1") (pin "6") (pinfunction "USB0_DM_6") (pintype "passive"))
    )
    (net (code "167") (name "USB_DP_TGTMCU") (class "Default")
      (node (ref "R2") (pin "2") (pinfunction "2_2") (pintype "passive"))
      (node (ref "U1") (pin "5") (pinfunction "USB0_DP_5") (pintype "passive"))
    )
    (net (code "168") (name "unconnected-(D23-PadTH)") (class "Default")
      (node (ref "D23") (pin "TH") (pinfunction "TH_TH") (pintype "power_in"))
    )
    (net (code "169") (name "unconnected-(D24-PadTH)") (class "Default")
      (node (ref "D24") (pin "TH") (pinfunction "TH_TH") (pintype "power_in"))
    )
    (net (code "170") (name "unconnected-(D28-PadTH)") (class "Default")
      (node (ref "D28") (pin "TH") (pinfunction "TH_TH") (pintype "power_in"))
    )
    (net (code "171") (name "unconnected-(D29-PadTH)") (class "Default")
      (node (ref "D29") (pin "TH") (pinfunction "TH_TH") (pintype "power_in"))
    )
    (net (code "172") (name "unconnected-(D33-PadTH)") (class "Default")
      (node (ref "D33") (pin "TH") (pinfunction "TH_TH") (pintype "power_in"))
    )
    (net (code "173") (name "unconnected-(D34-PadTH)") (class "Default")
      (node (ref "D34") (pin "TH") (pinfunction "TH_TH") (pintype "power_in"))
    )
    (net (code "174") (name "unconnected-(D38-PadTH)") (class "Default")
      (node (ref "D38") (pin "TH") (pinfunction "TH_TH") (pintype "power_in"))
    )
    (net (code "175") (name "unconnected-(D39-PadTH)") (class "Default")
      (node (ref "D39") (pin "TH") (pinfunction "TH_TH") (pintype "power_in"))
    )
    (net (code "176") (name "unconnected-(D43-PadTH)") (class "Default")
      (node (ref "D43") (pin "TH") (pinfunction "TH_TH") (pintype "power_in"))
    )
    (net (code "177") (name "unconnected-(D44-PadTH)") (class "Default")
      (node (ref "D44") (pin "TH") (pinfunction "TH_TH") (pintype "power_in"))
    )
    (net (code "178") (name "unconnected-(D48-PadTH)") (class "Default")
      (node (ref "D48") (pin "TH") (pinfunction "TH_TH") (pintype "power_in"))
    )
    (net (code "179") (name "unconnected-(D49-PadTH)") (class "Default")
      (node (ref "D49") (pin "TH") (pinfunction "TH_TH") (pintype "power_in"))
    )
    (net (code "180") (name "unconnected-(D53-PadTH)") (class "Default")
      (node (ref "D53") (pin "TH") (pinfunction "TH_TH") (pintype "power_in"))
    )
    (net (code "181") (name "unconnected-(D54-PadTH)") (class "Default")
      (node (ref "D54") (pin "TH") (pinfunction "TH_TH") (pintype "power_in"))
    )
    (net (code "182") (name "unconnected-(D58-PadTH)") (class "Default")
      (node (ref "D58") (pin "TH") (pinfunction "TH_TH") (pintype "power_in"))
    )
    (net (code "183") (name "unconnected-(D59-PadTH)") (class "Default")
      (node (ref "D59") (pin "TH") (pinfunction "TH_TH") (pintype "power_in"))
    )
    (net (code "184") (name "unconnected-(D63-PadTH)") (class "Default")
      (node (ref "D63") (pin "TH") (pinfunction "TH_TH") (pintype "power_in"))
    )
    (net (code "185") (name "unconnected-(D64-PadTH)") (class "Default")
      (node (ref "D64") (pin "TH") (pinfunction "TH_TH") (pintype "power_in"))
    )
    (net (code "186") (name "unconnected-(D65-PadTH)") (class "Default")
      (node (ref "D65") (pin "TH") (pinfunction "TH_TH") (pintype "power_in"))
    )
    (net (code "187") (name "unconnected-(D66-PadTH)") (class "Default")
      (node (ref "D66") (pin "TH") (pinfunction "TH_TH") (pintype "power_in"))
    )
    (net (code "188") (name "unconnected-(D70-PadTH)") (class "Default")
      (node (ref "D70") (pin "TH") (pinfunction "TH_TH") (pintype "power_in"))
    )
    (net (code "189") (name "unconnected-(D71-PadTH)") (class "Default")
      (node (ref "D71") (pin "TH") (pinfunction "TH_TH") (pintype "power_in"))
    )
    (net (code "190") (name "unconnected-(D72-PadTH)") (class "Default")
      (node (ref "D72") (pin "TH") (pinfunction "TH_TH") (pintype "power_in"))
    )
    (net (code "191") (name "unconnected-(D73-PadTH)") (class "Default")
      (node (ref "D73") (pin "TH") (pinfunction "TH_TH") (pintype "power_in"))
    )
    (net (code "192") (name "unconnected-(IC5-CBUS2-Pad10)") (class "Default")
      (node (ref "IC5") (pin "10") (pinfunction "CBUS2_10") (pintype "bidirectional"))
    )
    (net (code "193") (name "unconnected-(IC5-CBUS4-Pad9)") (class "Default")
      (node (ref "IC5") (pin "9") (pinfunction "CBUS4_9") (pintype "bidirectional"))
    )
    (net (code "194") (name "unconnected-(IC5-OSCI-Pad27)") (class "Default")
      (node (ref "IC5") (pin "27") (pinfunction "OSCI_27") (pintype "input"))
    )
    (net (code "195") (name "unconnected-(IC5-OSCO-Pad28)") (class "Default")
      (node (ref "IC5") (pin "28") (pinfunction "OSCO_28") (pintype "output"))
    )
    (net (code "196") (name "unconnected-(IC5-~{CTS}-Pad8)") (class "Default")
      (node (ref "IC5") (pin "8") (pinfunction "~{CTS}_8") (pintype "input"))
    )
    (net (code "197") (name "unconnected-(IC5-~{DCD}-Pad7)") (class "Default")
      (node (ref "IC5") (pin "7") (pinfunction "~{DCD}_7") (pintype "input"))
    )
    (net (code "198") (name "unconnected-(IC5-~{DSR}-Pad6)") (class "Default")
      (node (ref "IC5") (pin "6") (pinfunction "~{DSR}_6") (pintype "input"))
    )
    (net (code "199") (name "unconnected-(IC5-~{DTR}-Pad31)") (class "Default")
      (node (ref "IC5") (pin "31") (pinfunction "~{DTR}_31") (pintype "output"))
    )
    (net (code "200") (name "unconnected-(IC5-~{RI}-Pad3)") (class "Default")
      (node (ref "IC5") (pin "3") (pinfunction "~{RI}_3") (pintype "input"))
    )
    (net (code "201") (name "unconnected-(IC5-~{RTS}-Pad32)") (class "Default")
      (node (ref "IC5") (pin "32") (pinfunction "~{RTS}_32") (pintype "output"))
    )
    (net (code "202") (name "unconnected-(PROG-Pad8)") (class "Default")
      (node (ref "PROG") (pin "8") (pinfunction "8_8") (pintype "passive"))
    )
    (net (code "203") (name "unconnected-(PROG-Pad9)") (class "Default")
      (node (ref "PROG") (pin "9") (pinfunction "9_9") (pintype "passive"))
    )
    (net (code "204") (name "unconnected-(X1-ID-Pad4)") (class "Default")
      (node (ref "X1") (pin "4") (pinfunction "ID_4") (pintype "passive"))
    )
    (net (code "205") (name "unconnected-(X2-ID-Pad4)") (class "Default")
      (node (ref "X2") (pin "4") (pinfunction "ID_4") (pintype "passive"))
    )
  )
)
